# barometer.net
KiCad netlist of a schematic drawn in EAGLE
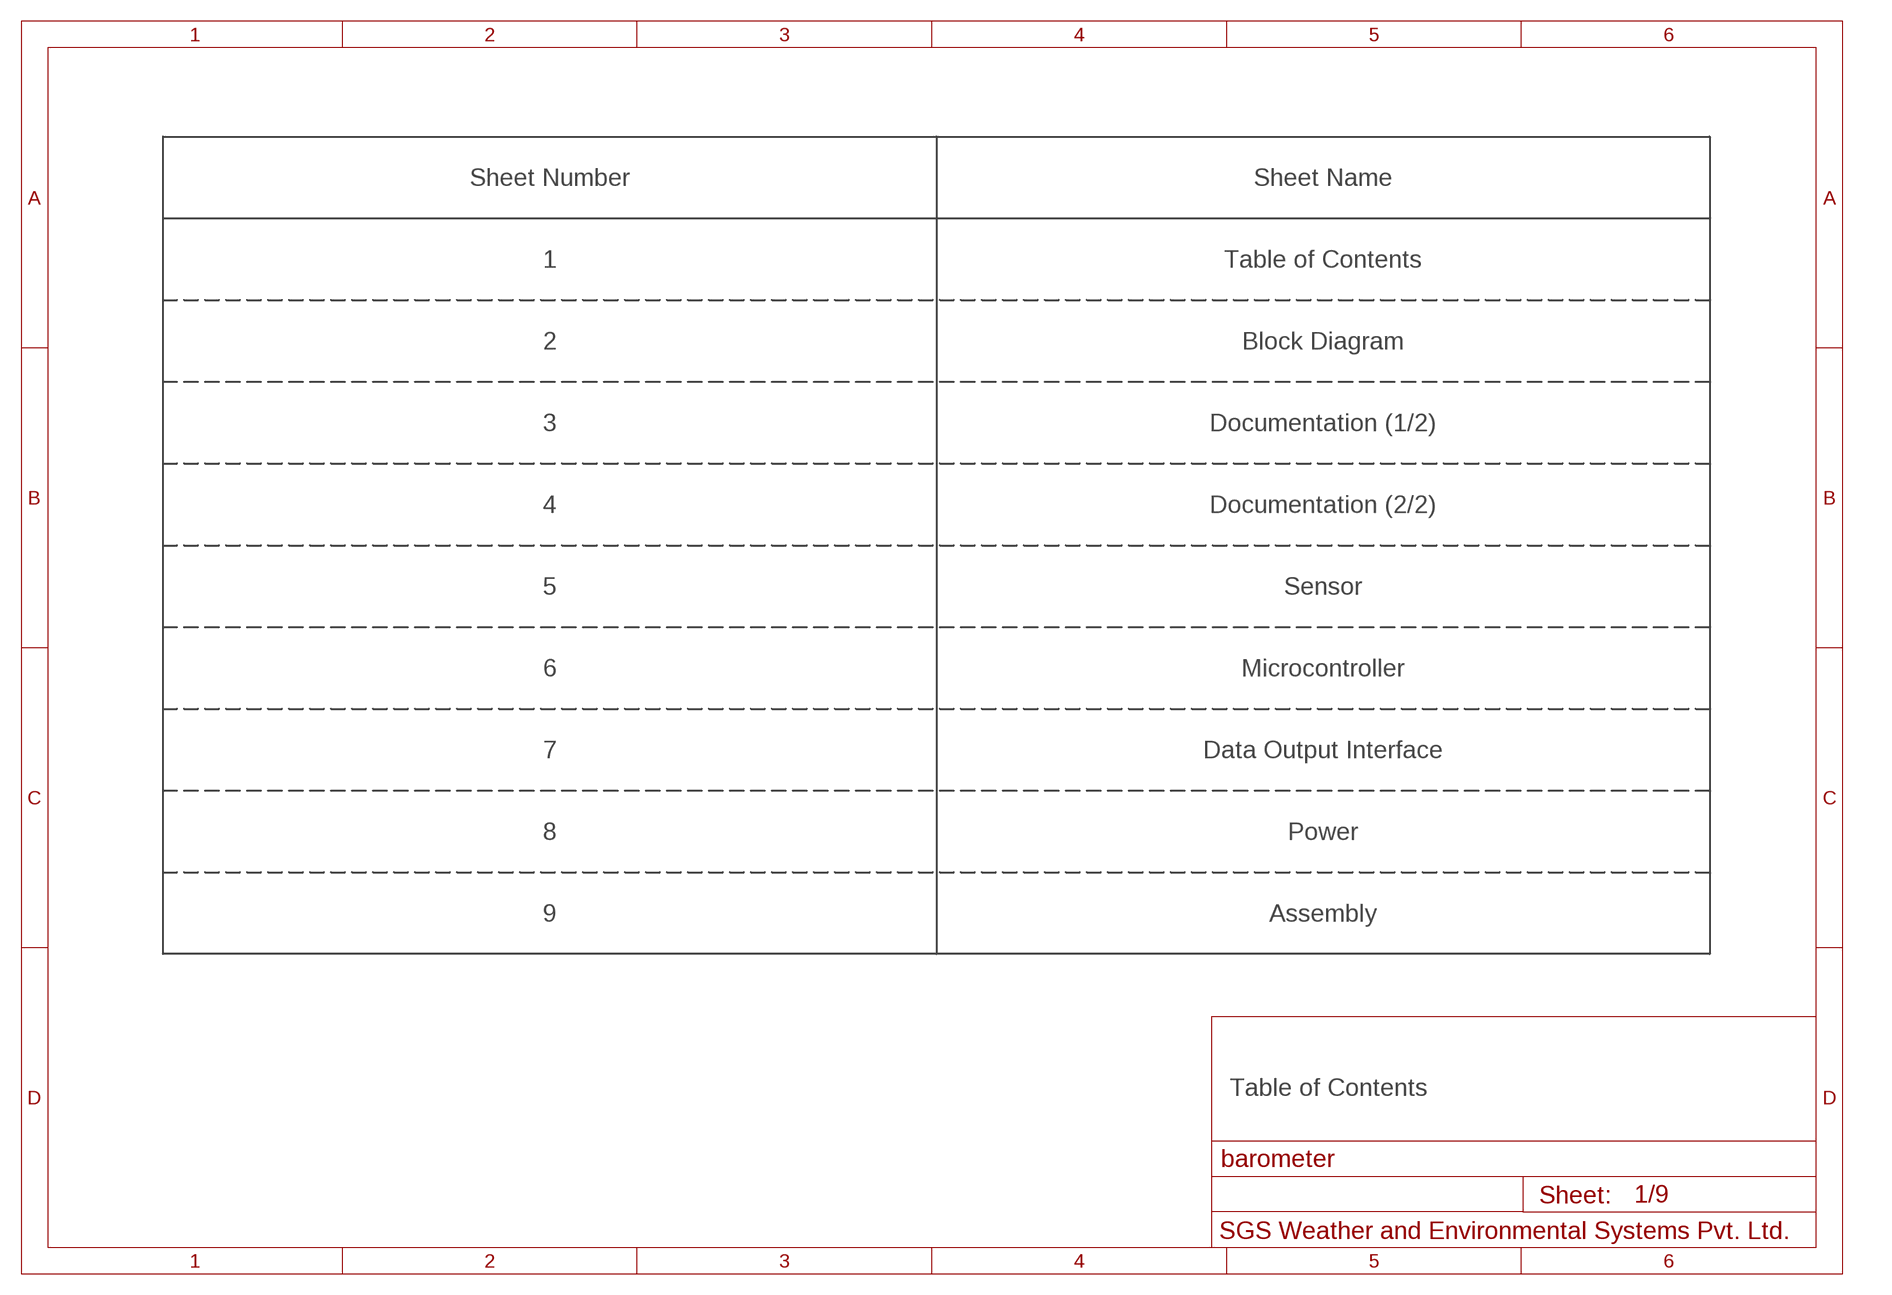
[diagram p0: schematic, sheet 1]
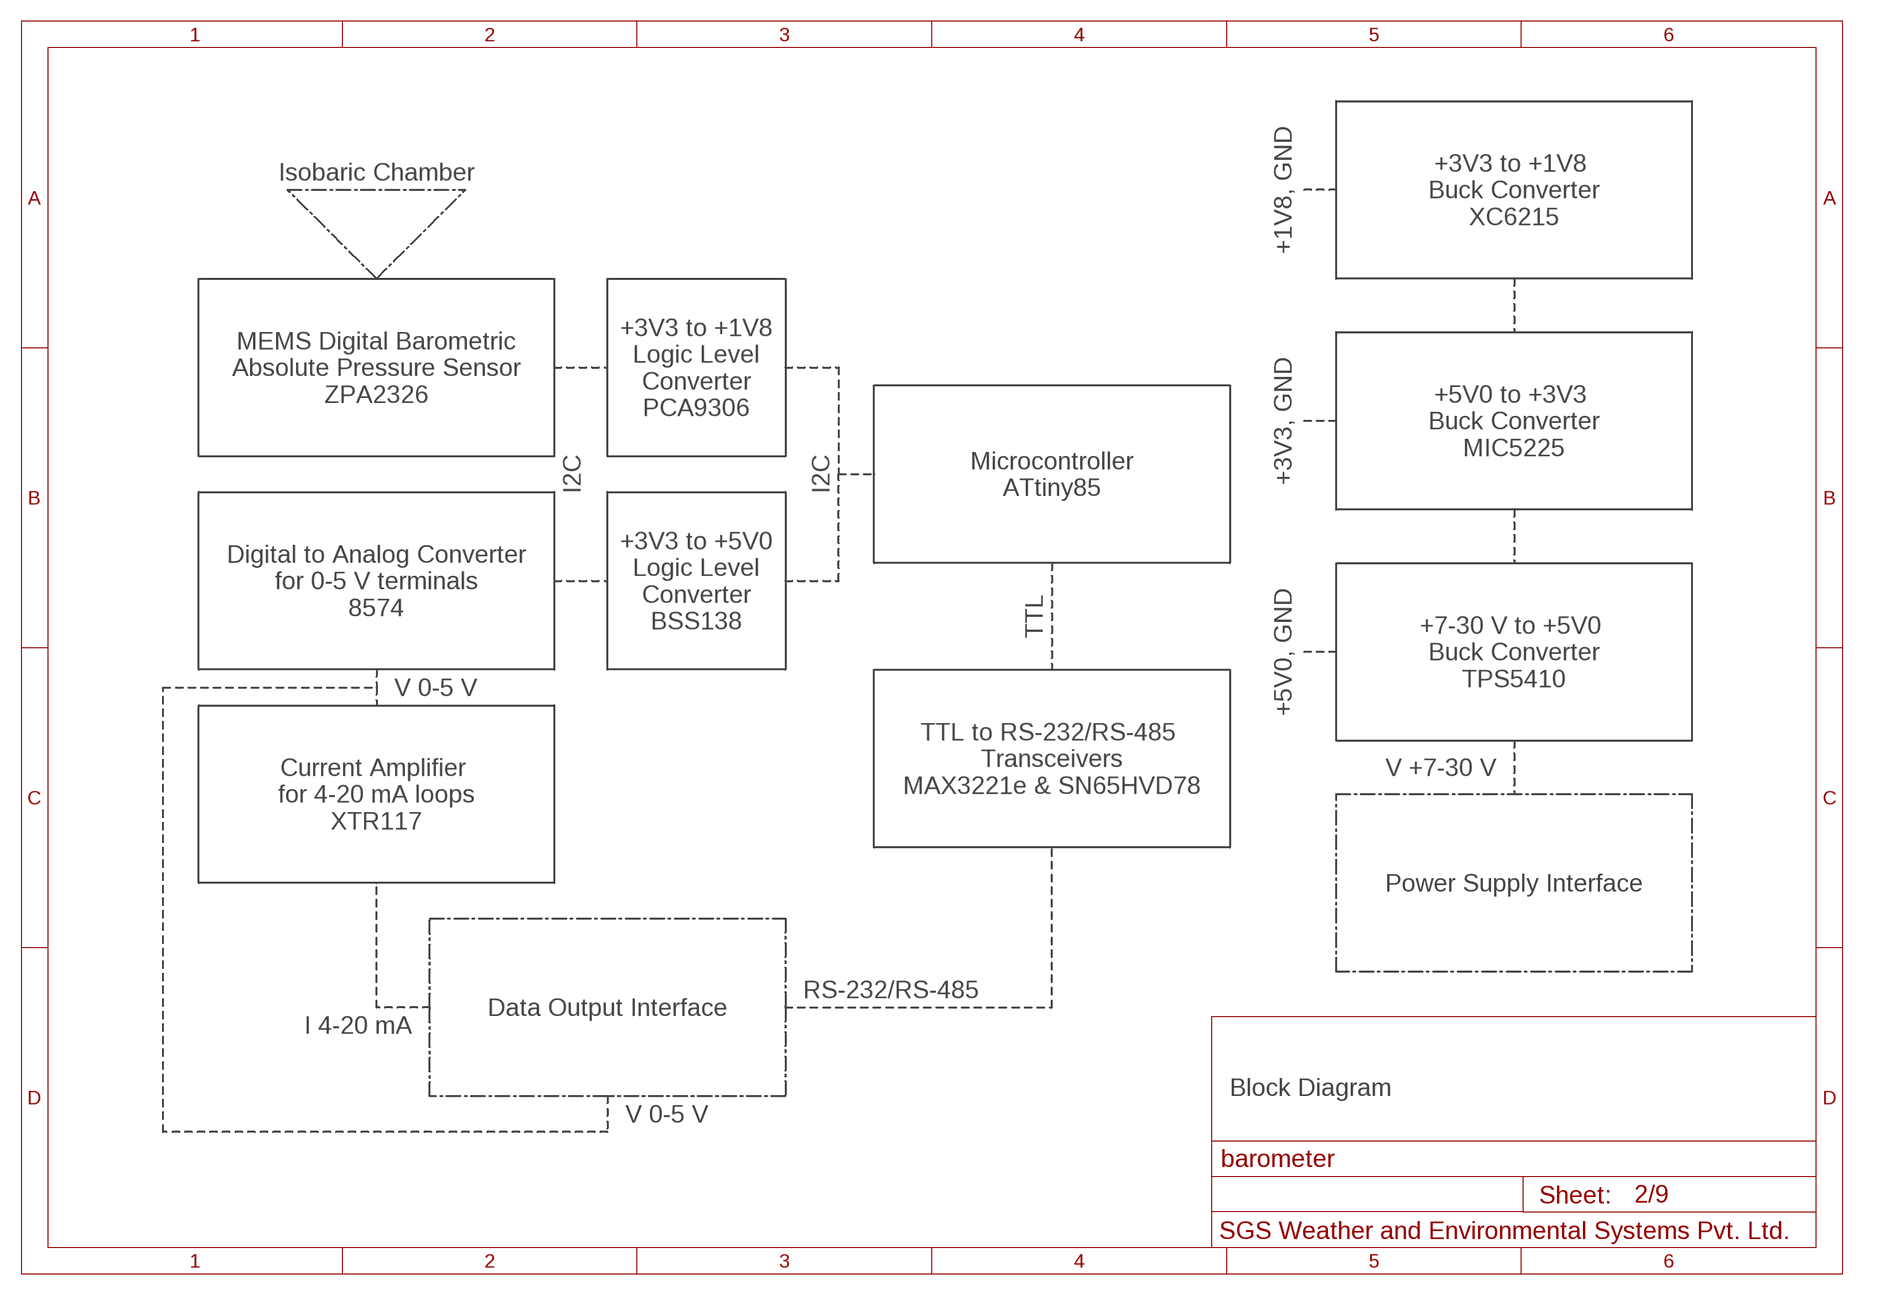
[diagram p1: schematic, sheet 2]
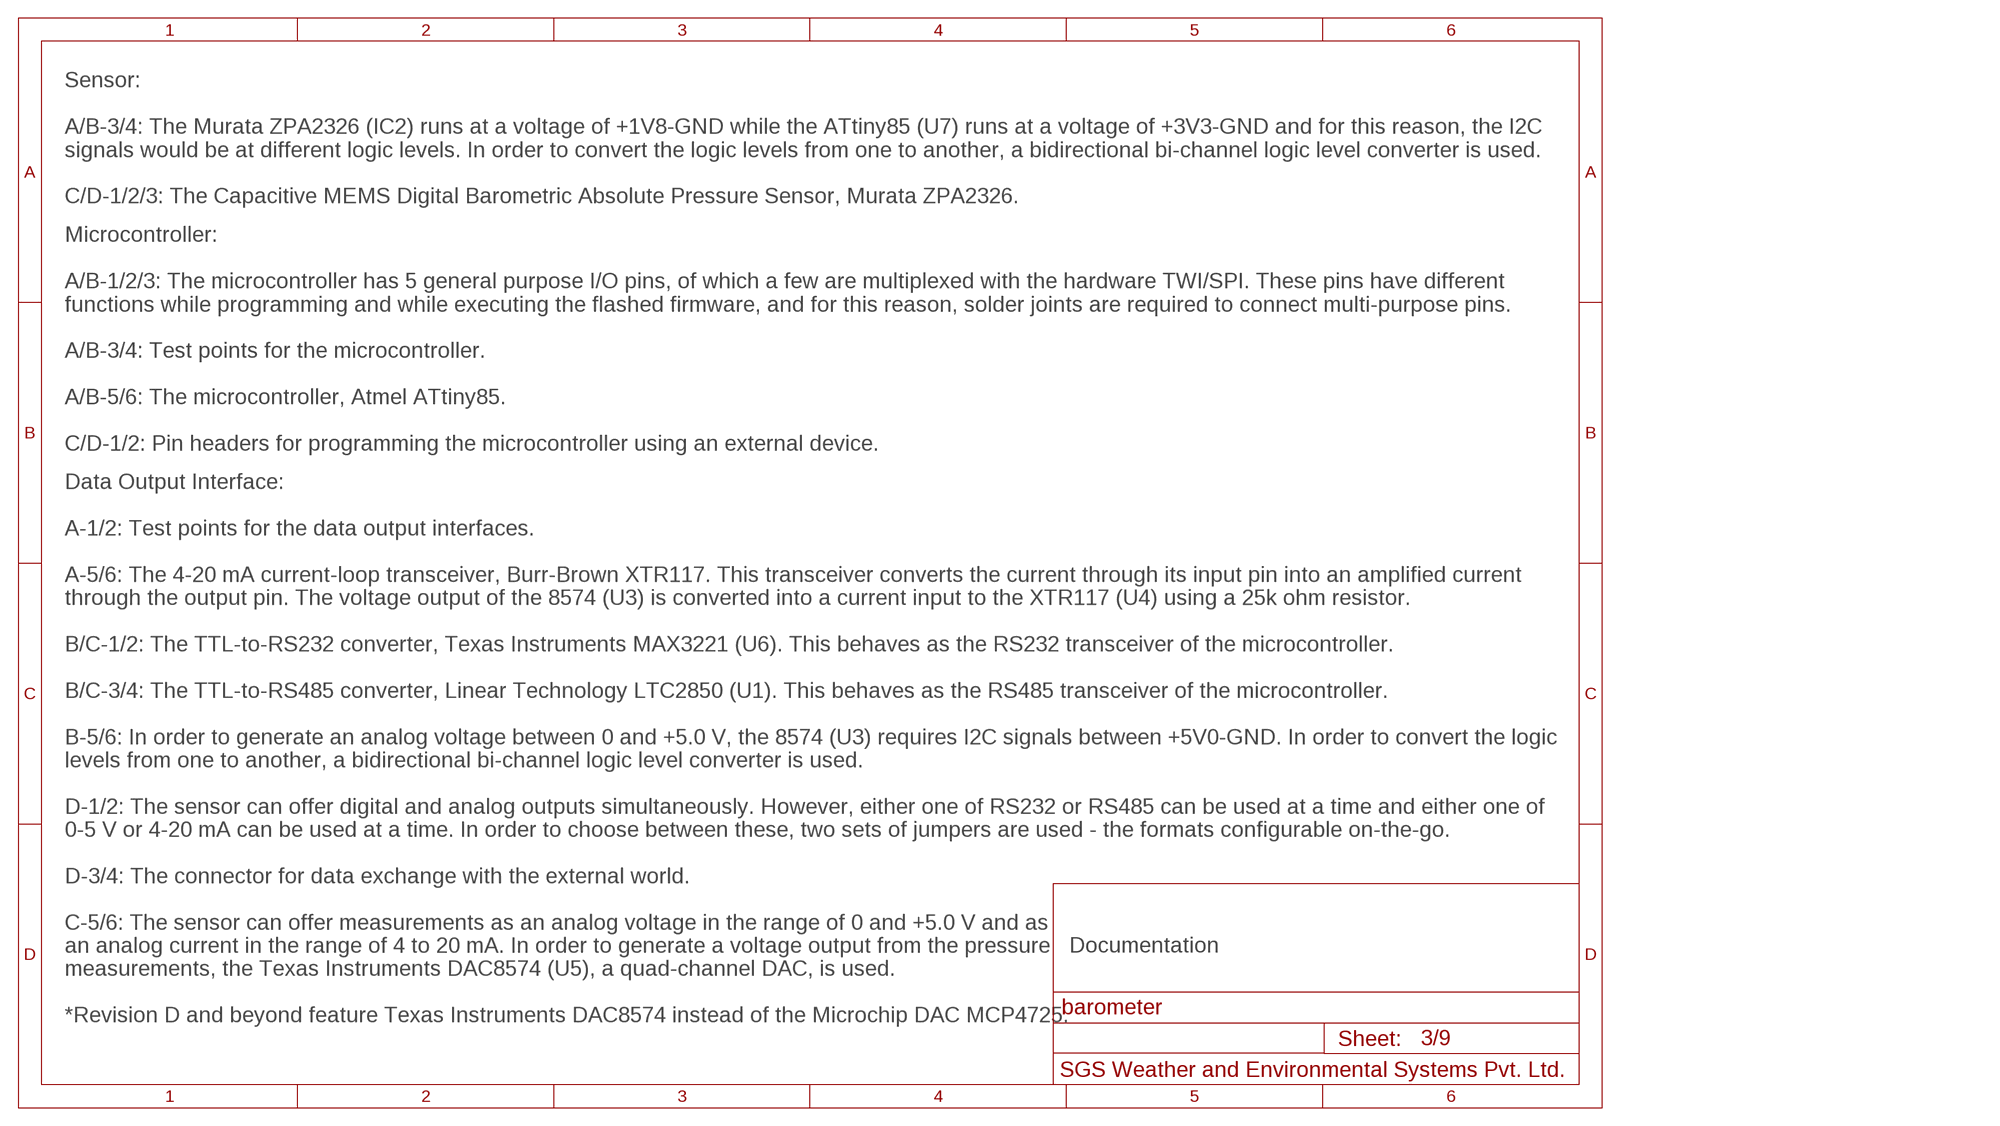
[diagram p2: schematic, sheet 3]
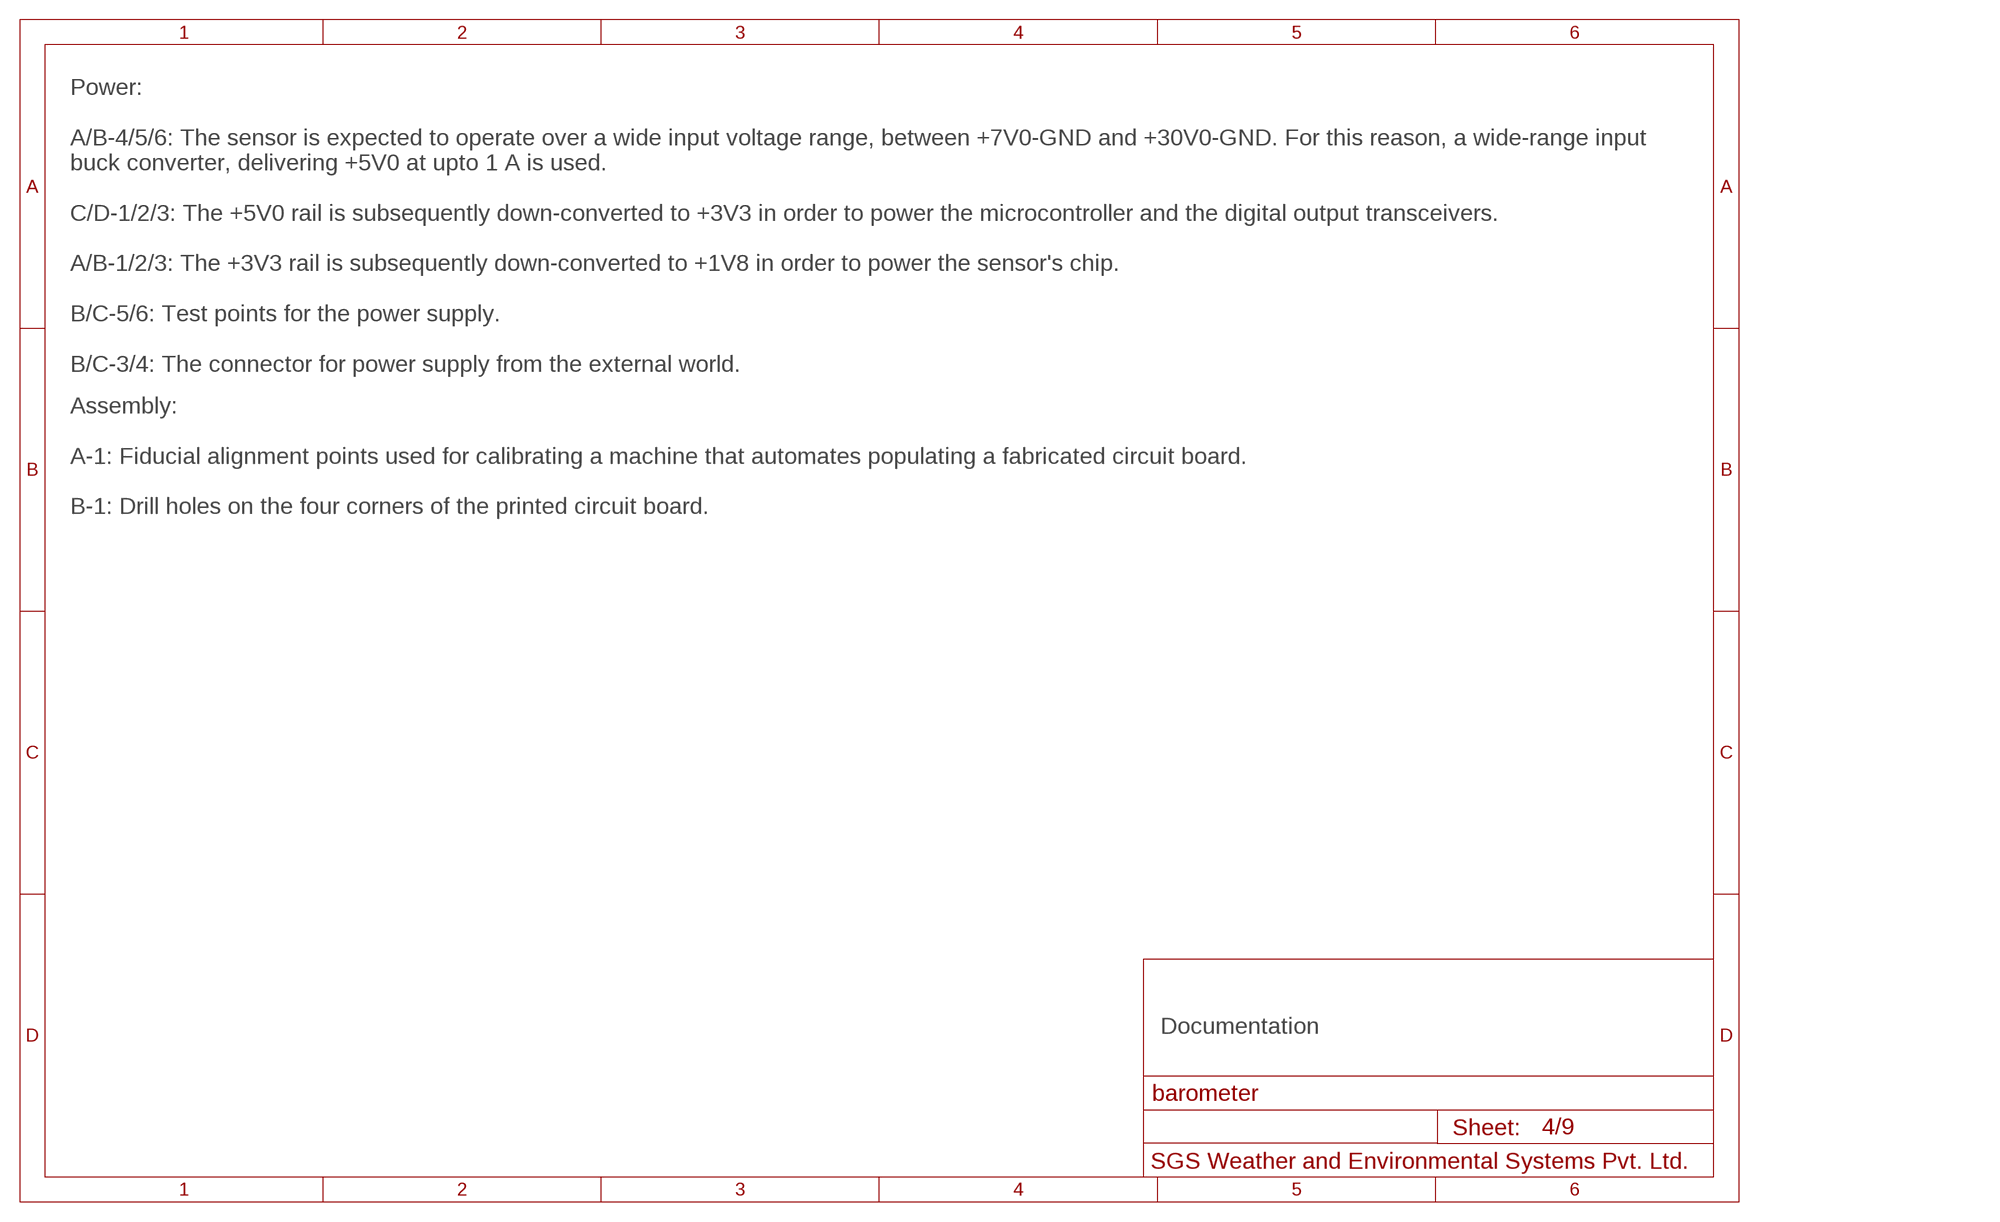
[diagram p3: schematic, sheet 4]
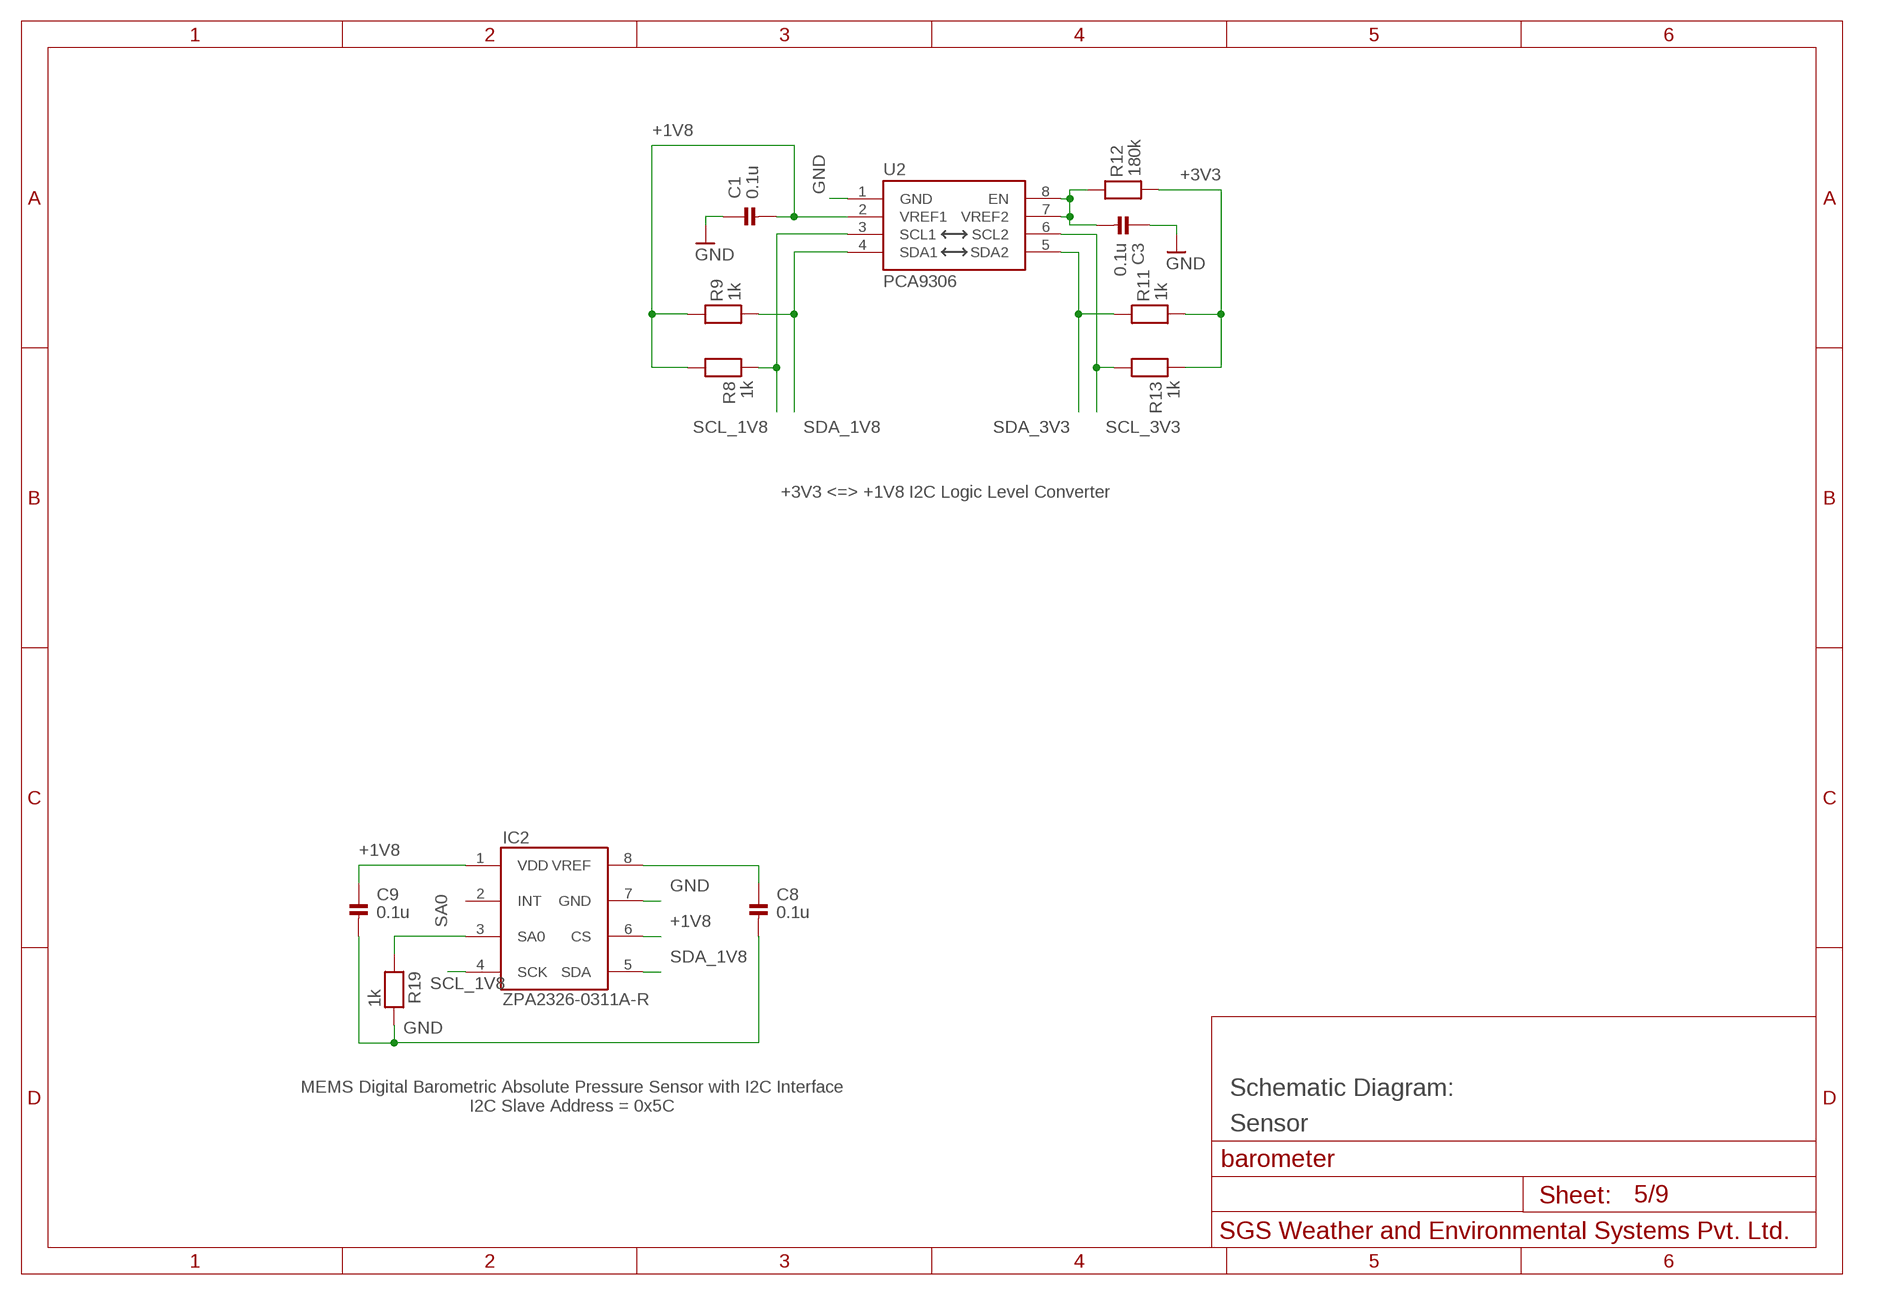
[diagram p4: schematic, sheet 5]
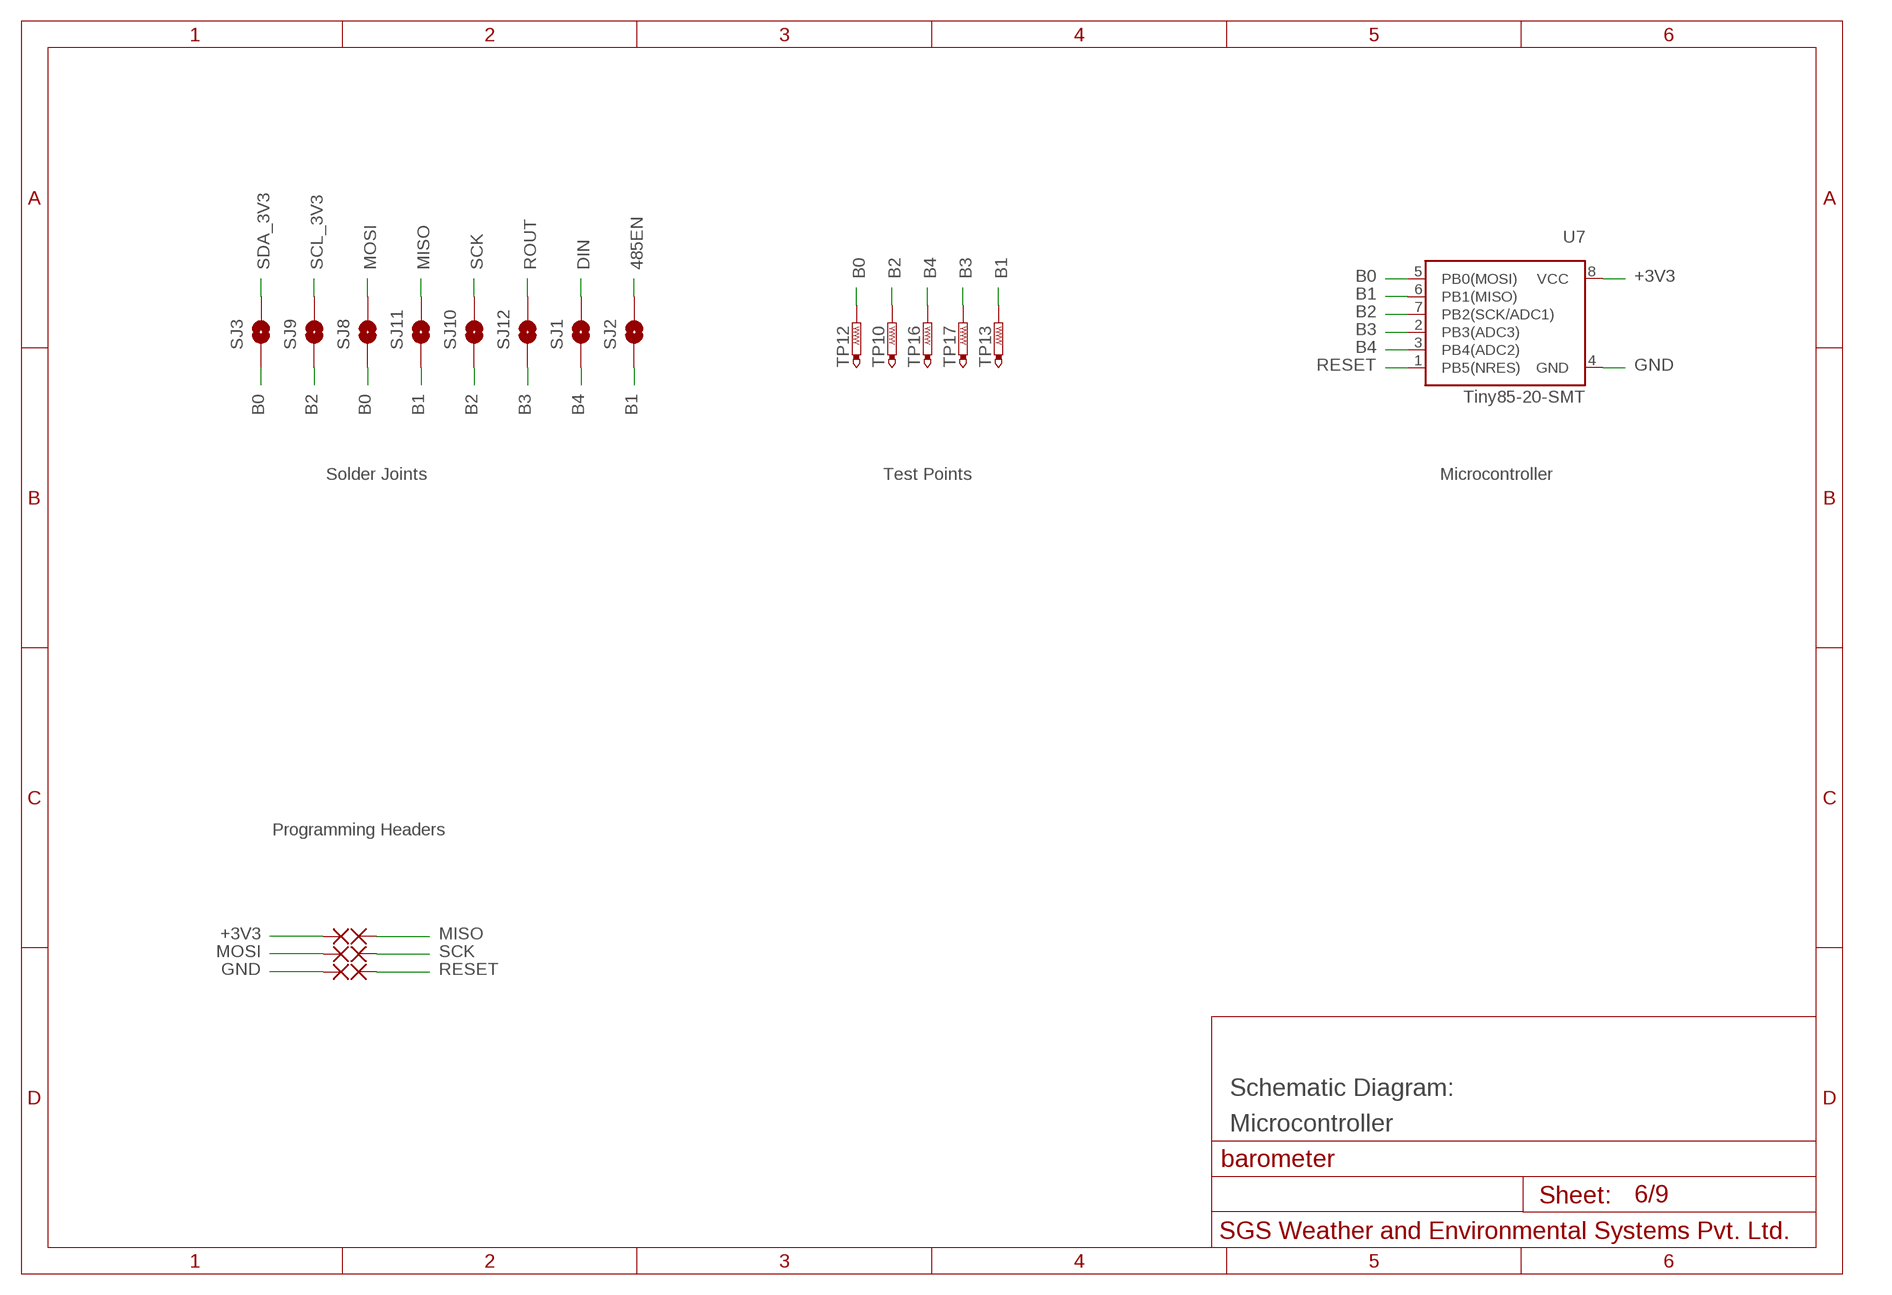
[diagram p5: schematic, sheet 6]
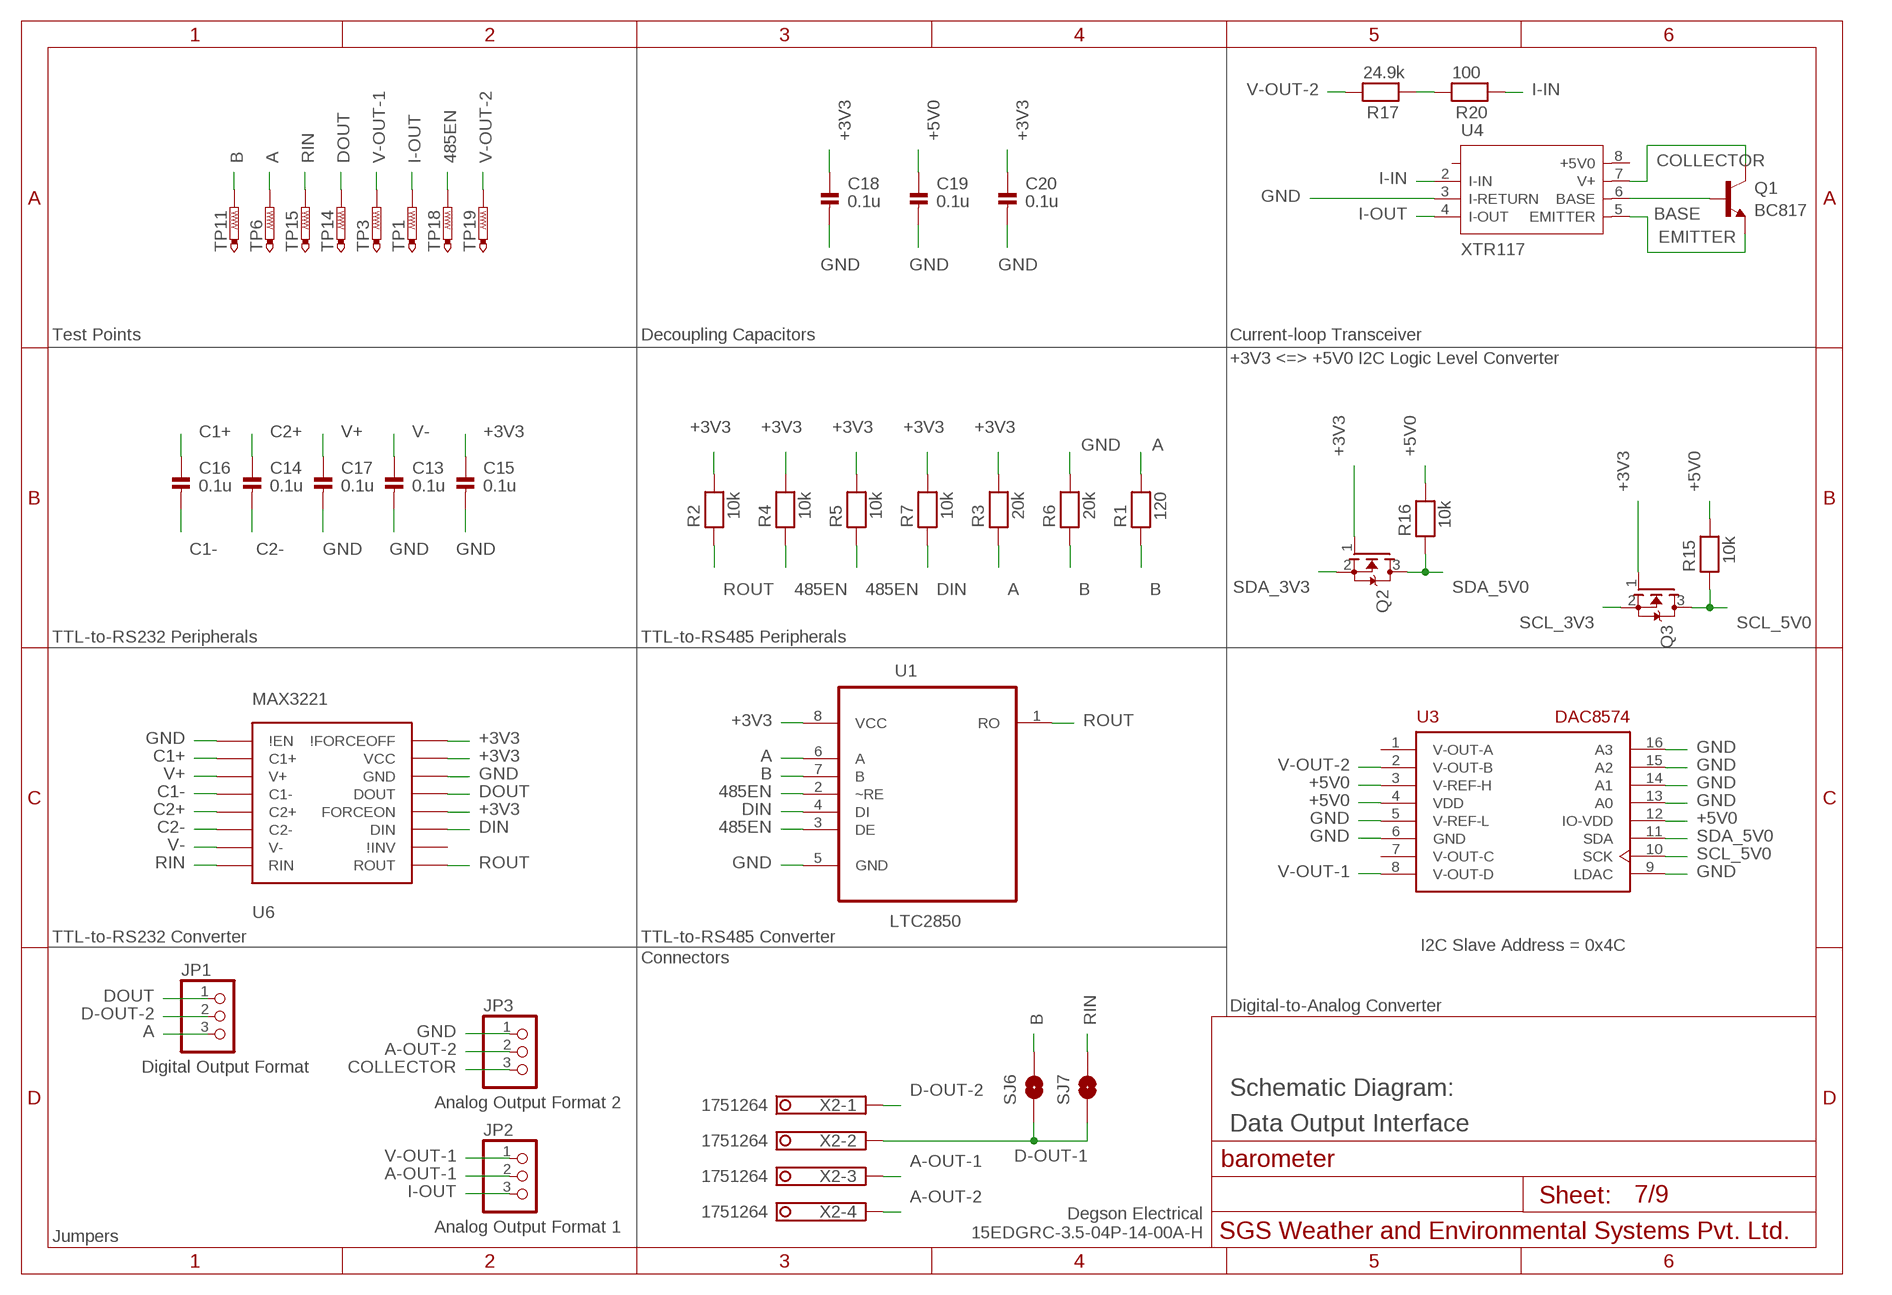
[diagram p6: schematic, sheet 7]
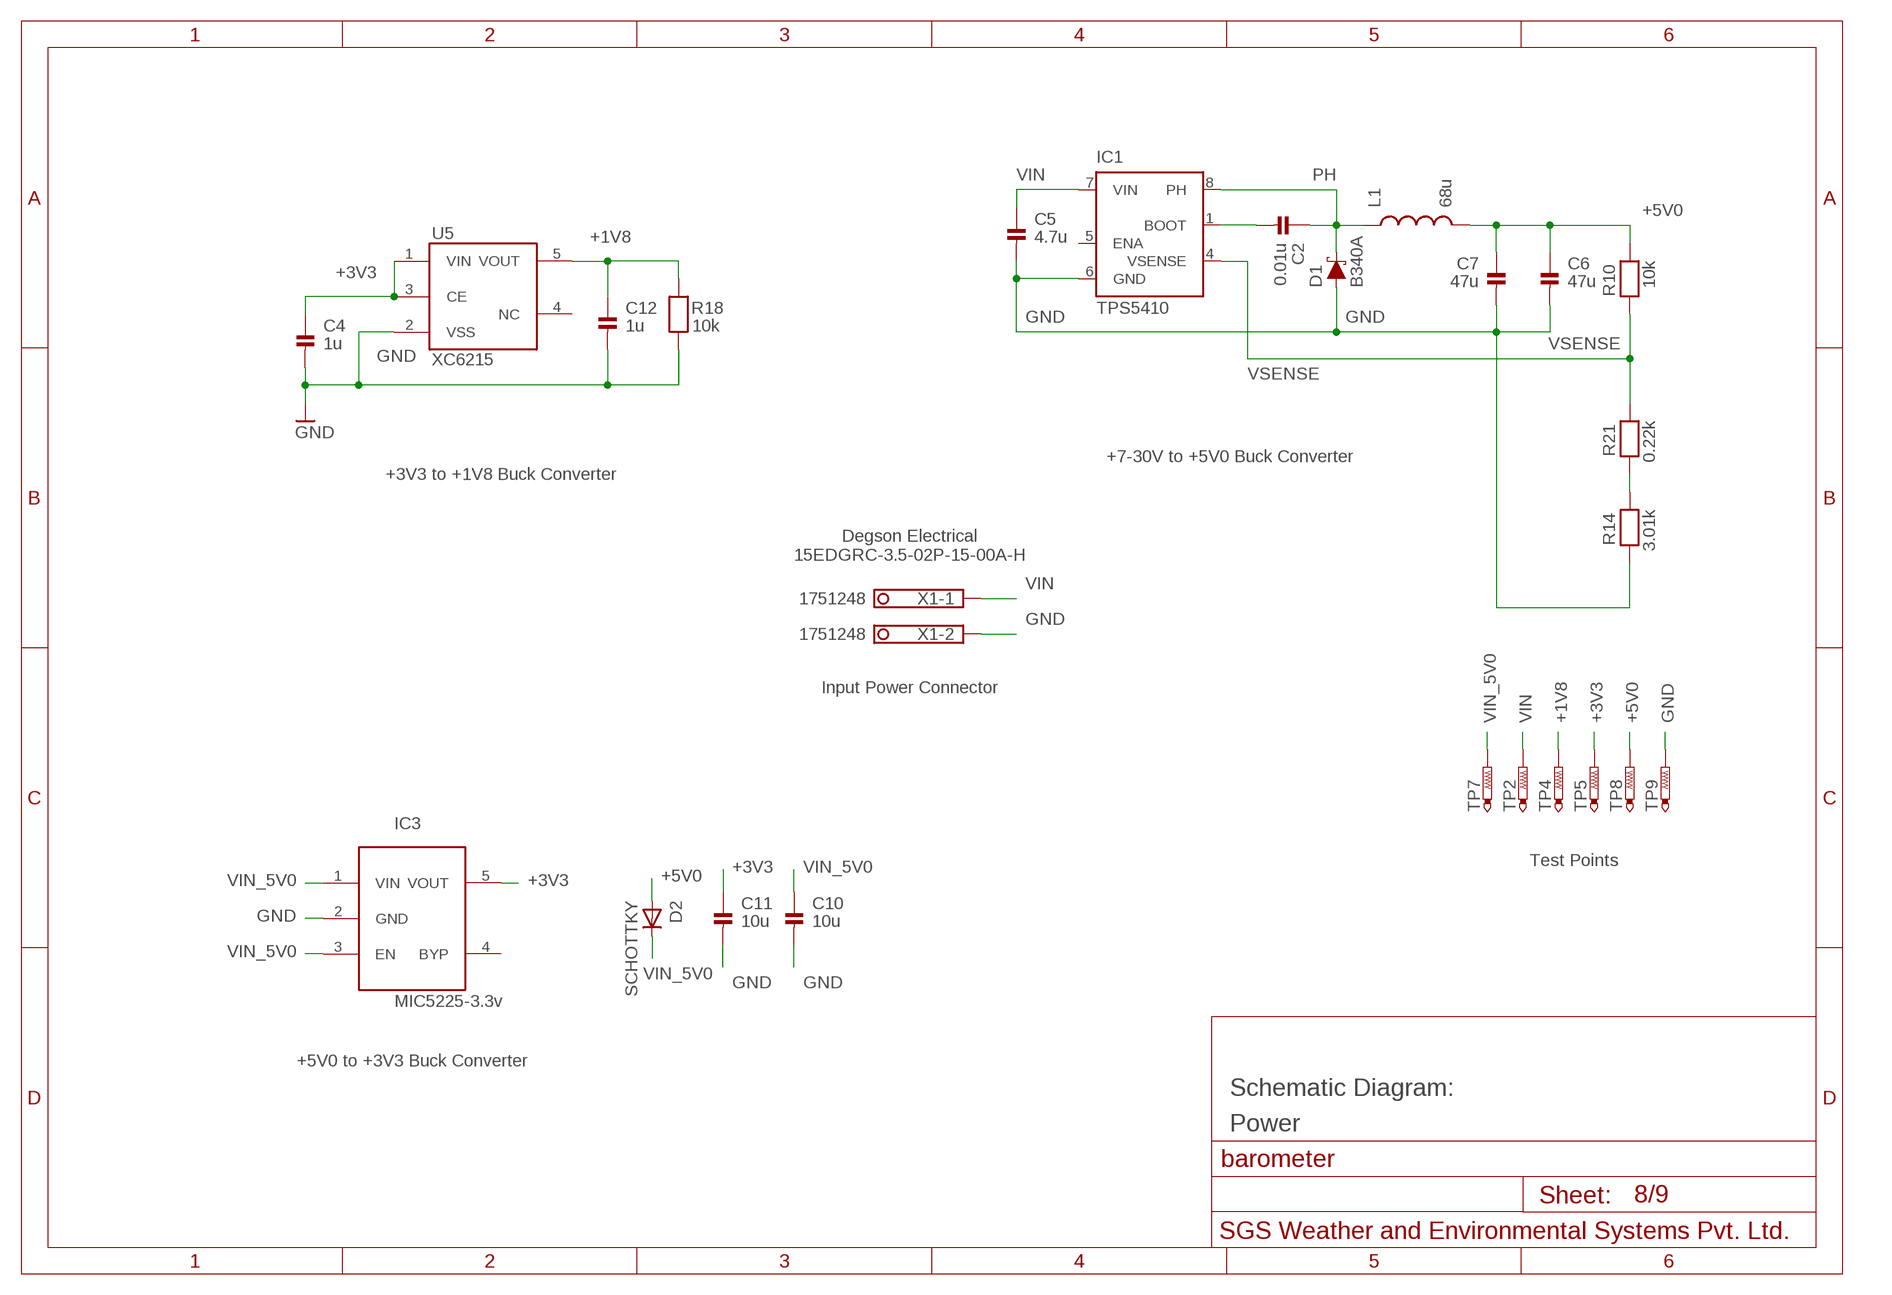
[diagram p7: schematic, sheet 8]
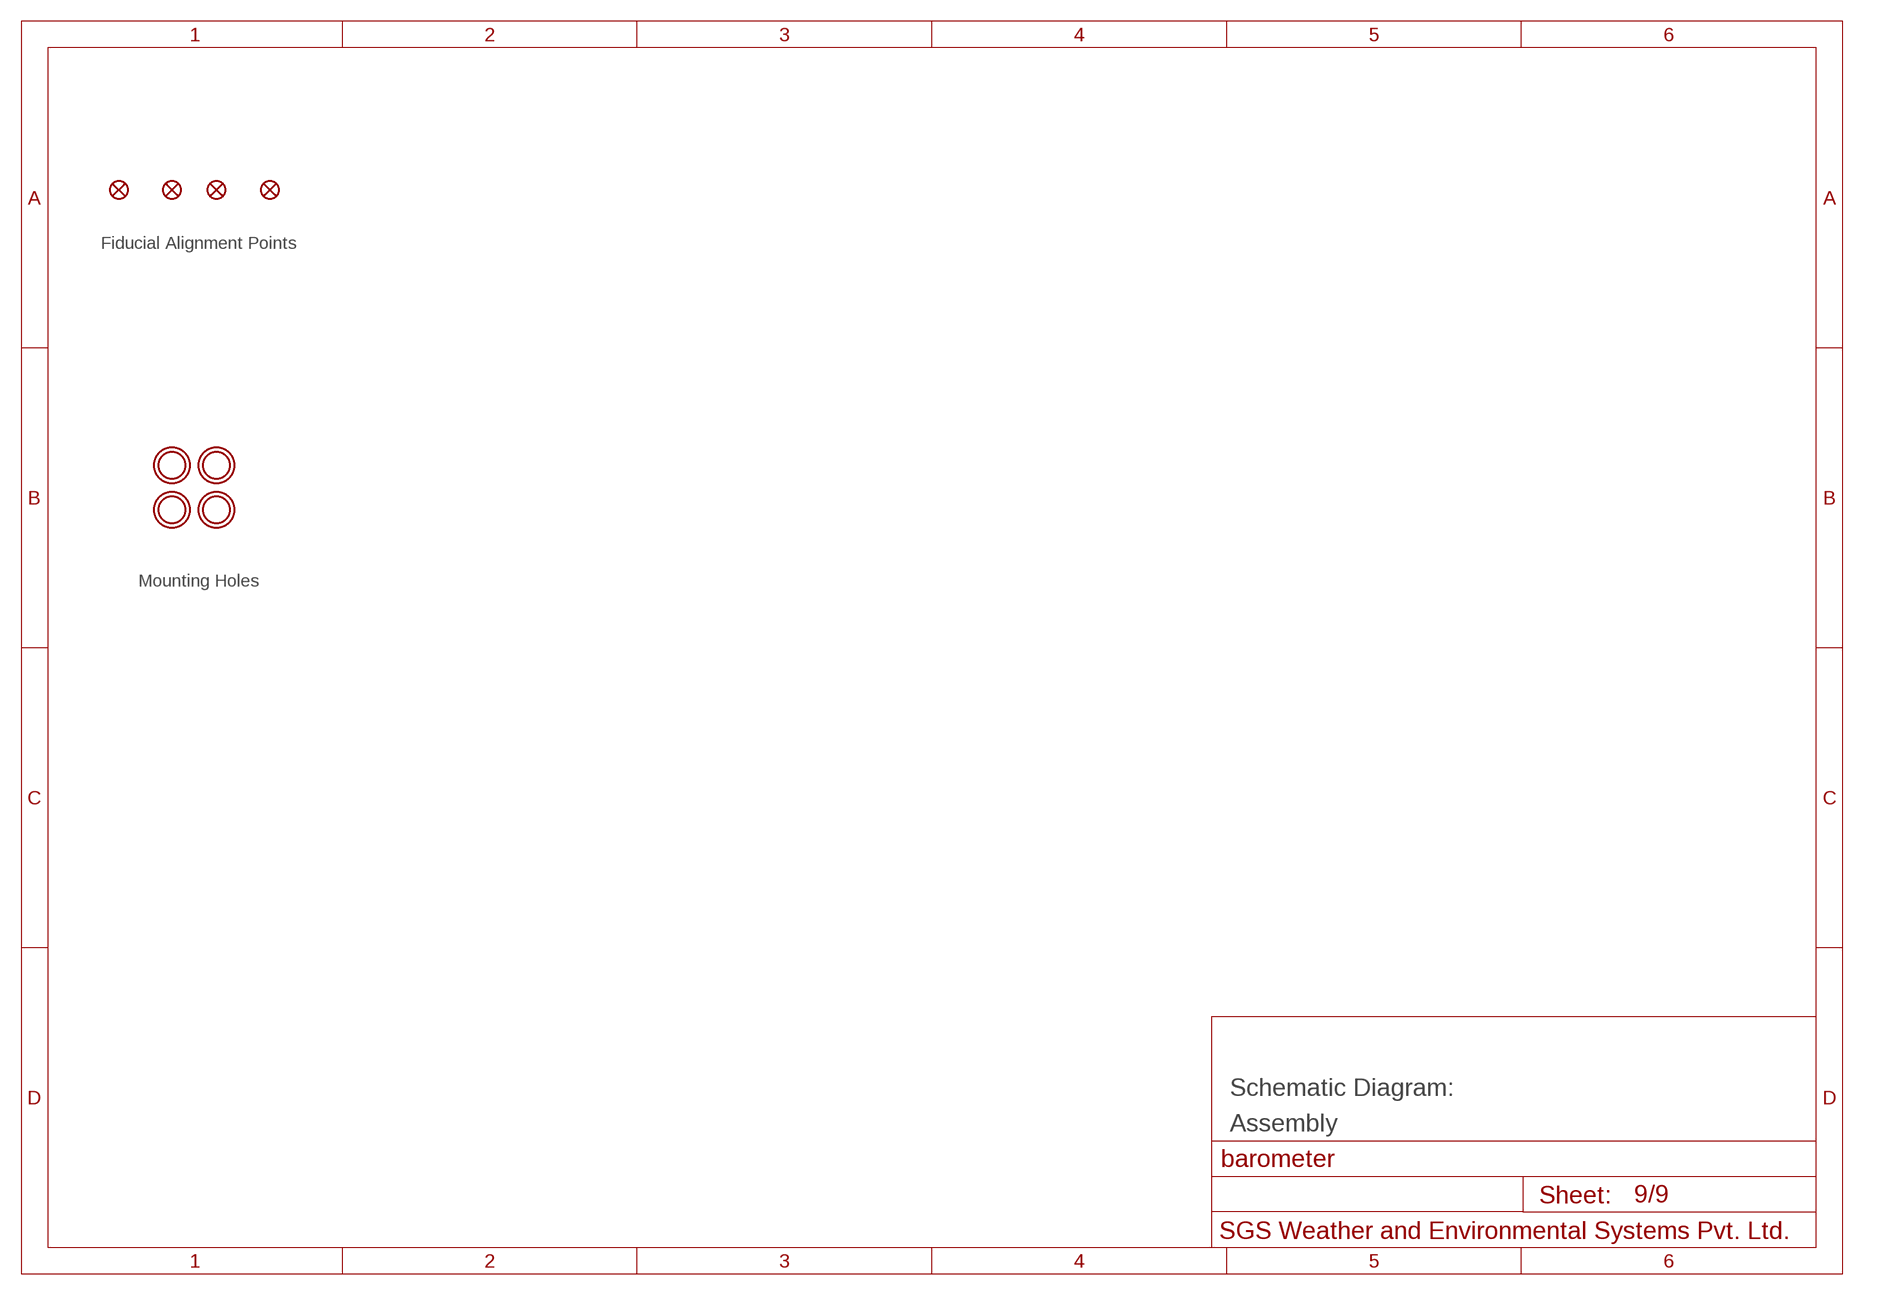
[diagram p8: schematic, sheet 9]

(export (version "E")
  (design (tool "Eeschema 10.0.6"))
  (components
    (comp (ref "C13")
      (value "0.1u")
      (footprint "eagle-import:0603")
      (libsource (lib "eagle-import") (part "CAP_CERAMIC0603"))
    )
    (comp (ref "C14")
      (value "0.1u")
      (footprint "eagle-import:0603")
      (libsource (lib "eagle-import") (part "CAP_CERAMIC0603"))
    )
    (comp (ref "C15")
      (value "0.1u")
      (footprint "eagle-import:0603")
      (libsource (lib "eagle-import") (part "CAP_CERAMIC0603"))
    )
    (comp (ref "C16")
      (value "0.1u")
      (footprint "eagle-import:0603")
      (libsource (lib "eagle-import") (part "CAP_CERAMIC0603"))
    )
    (comp (ref "C17")
      (value "0.1u")
      (footprint "eagle-import:0603")
      (libsource (lib "eagle-import") (part "CAP_CERAMIC0603"))
    )
    (comp (ref "C18")
      (value "0.1u")
      (footprint "eagle-import:0603")
      (libsource (lib "eagle-import") (part "CAP_CERAMIC0603"))
    )
    (comp (ref "C19")
      (value "0.1u")
      (footprint "eagle-import:0603")
      (libsource (lib "eagle-import") (part "CAP_CERAMIC0603"))
    )
    (comp (ref "C20")
      (value "0.1u")
      (footprint "eagle-import:0603")
      (libsource (lib "eagle-import") (part "CAP_CERAMIC0603"))
    )
    (comp (ref "JP1")
      (value "Digital Output Format")
      (footprint "eagle-import:1X03_SMT")
      (libsource (lib "eagle-import") (part "HEADER-1X3SMT"))
    )
    (comp (ref "JP2")
      (value "Analog Output Format 1")
      (footprint "eagle-import:1X03_SMT")
      (libsource (lib "eagle-import") (part "HEADER-1X3SMT"))
    )
    (comp (ref "JP3")
      (value "Analog Output Format 2")
      (footprint "eagle-import:1X03_SMT")
      (libsource (lib "eagle-import") (part "HEADER-1X3SMT"))
    )
    (comp (ref "Q1")
      (value "BC817")
      (footprint "eagle-import:SOT23-WIDE")
      (libsource (lib "eagle-import") (part "TRANSISTOR_NPNWIDE"))
    )
    (comp (ref "Q2")
      (value "MOSFET-NWIDE")
      (footprint "eagle-import:SOT23-WIDE")
      (libsource (lib "eagle-import") (part "MOSFET-NWIDE"))
    )
    (comp (ref "Q3")
      (value "MOSFET-NWIDE")
      (footprint "eagle-import:SOT23-WIDE")
      (libsource (lib "eagle-import") (part "MOSFET-NWIDE"))
    )
    (comp (ref "R1")
      (value "120")
      (footprint "eagle-import:0603")
      (libsource (lib "eagle-import") (part "RESISTOR0603"))
    )
    (comp (ref "R2")
      (value "10k")
      (footprint "eagle-import:0603")
      (libsource (lib "eagle-import") (part "RESISTOR0603"))
    )
    (comp (ref "R3")
      (value "20k")
      (footprint "eagle-import:0603")
      (libsource (lib "eagle-import") (part "RESISTOR0603"))
    )
    (comp (ref "R4")
      (value "10k")
      (footprint "eagle-import:0603")
      (libsource (lib "eagle-import") (part "RESISTOR0603"))
    )
    (comp (ref "R5")
      (value "10k")
      (footprint "eagle-import:0603")
      (libsource (lib "eagle-import") (part "RESISTOR0603"))
    )
    (comp (ref "R6")
      (value "20k")
      (footprint "eagle-import:0603")
      (libsource (lib "eagle-import") (part "RESISTOR0603"))
    )
    (comp (ref "R7")
      (value "10k")
      (footprint "eagle-import:0603")
      (libsource (lib "eagle-import") (part "RESISTOR0603"))
    )
    (comp (ref "R15")
      (value "10k")
      (footprint "eagle-import:0603")
      (libsource (lib "eagle-import") (part "RESISTOR0603"))
    )
    (comp (ref "R16")
      (value "10k")
      (footprint "eagle-import:0603")
      (libsource (lib "eagle-import") (part "RESISTOR0603"))
    )
    (comp (ref "R17")
      (value "24.9k")
      (footprint "eagle-import:0603")
      (libsource (lib "eagle-import") (part "RESISTOR0603"))
    )
    (comp (ref "R20")
      (value "100")
      (footprint "eagle-import:0603")
      (libsource (lib "eagle-import") (part "RESISTOR0603"))
    )
    (comp (ref "SJ6")
      (value "SOLDERJUMPERTRACE")
      (footprint "eagle-import:SJ_2S-TRACE")
      (libsource (lib "eagle-import") (part "SOLDERJUMPERTRACE"))
    )
    (comp (ref "SJ7")
      (value "SOLDERJUMPERTRACE")
      (footprint "eagle-import:SJ_2S-TRACE")
      (libsource (lib "eagle-import") (part "SOLDERJUMPERTRACE"))
    )
    (comp (ref "TP1")
      (value "PTR1B1,27")
      (footprint "eagle-import:B1,27")
      (libsource (lib "eagle-import") (part "PTR1B1,27"))
    )
    (comp (ref "TP3")
      (value "PTR1B1,27")
      (footprint "eagle-import:B1,27")
      (libsource (lib "eagle-import") (part "PTR1B1,27"))
    )
    (comp (ref "TP6")
      (value "PTR1B1,27")
      (footprint "eagle-import:B1,27")
      (libsource (lib "eagle-import") (part "PTR1B1,27"))
    )
    (comp (ref "TP11")
      (value "PTR1B1,27")
      (footprint "eagle-import:B1,27")
      (libsource (lib "eagle-import") (part "PTR1B1,27"))
    )
    (comp (ref "TP14")
      (value "PTR1B1,27")
      (footprint "eagle-import:B1,27")
      (libsource (lib "eagle-import") (part "PTR1B1,27"))
    )
    (comp (ref "TP15")
      (value "PTR1B1,27")
      (footprint "eagle-import:B1,27")
      (libsource (lib "eagle-import") (part "PTR1B1,27"))
    )
    (comp (ref "TP18")
      (value "PTR1B1,27")
      (footprint "eagle-import:B1,27")
      (libsource (lib "eagle-import") (part "PTR1B1,27"))
    )
    (comp (ref "TP19")
      (value "PTR1B1,27")
      (footprint "eagle-import:B1,27")
      (libsource (lib "eagle-import") (part "PTR1B1,27"))
    )
    (comp (ref "U1")
      (value "LTC2850")
      (footprint "eagle-import:SOIC127P600X175-8N")
      (fields (field (name "MPN") "LTC2850IS8#PBF"))
      (libsource (lib "eagle-import") (part "LTC2850IS8PBF"))
    )
    (comp (ref "U3")
      (value "DAC8574")
      (footprint "eagle-import:TSSOP16")
      (libsource (lib "eagle-import") (part "DAC8574"))
    )
    (comp (ref "U4")
      (value "XTR117")
      (footprint "eagle-import:MSOP8-0.65-3X3MM")
      (libsource (lib "eagle-import") (part "TRANSCEIVER-XTR117"))
    )
    (comp (ref "U6")
      (value "MAX3221")
      (footprint "eagle-import:TSSOP16")
      (libsource (lib "eagle-import") (part "MAX3221-TSSOP16"))
    )
    (comp (ref "X2")
      (value "1751264")
      (footprint "eagle-import:1751264")
      (libsource (lib "eagle-import") (part "1751264"))
    )
    (comp (ref "C1")
      (value "0.1u")
      (footprint "eagle-import:0603")
      (libsource (lib "eagle-import") (part "CAP_CERAMIC0603"))
    )
    (comp (ref "C3")
      (value "0.1u")
      (footprint "eagle-import:0603")
      (libsource (lib "eagle-import") (part "CAP_CERAMIC0603"))
    )
    (comp (ref "C8")
      (value "0.1u")
      (footprint "eagle-import:0603")
      (libsource (lib "eagle-import") (part "CAP_CERAMIC0603"))
    )
    (comp (ref "C9")
      (value "0.1u")
      (footprint "eagle-import:0603")
      (libsource (lib "eagle-import") (part "CAP_CERAMIC0603"))
    )
    (comp (ref "IC2")
      (value "ZPA2326-0311A-R")
      (footprint "eagle-import:2326")
      (libsource (lib "eagle-import") (part "ZPA2326-0311A-R"))
    )
    (comp (ref "R8")
      (value "1k")
      (footprint "eagle-import:0603")
      (libsource (lib "eagle-import") (part "RESISTOR0603"))
    )
    (comp (ref "R9")
      (value "1k")
      (footprint "eagle-import:0603")
      (libsource (lib "eagle-import") (part "RESISTOR0603"))
    )
    (comp (ref "R11")
      (value "1k")
      (footprint "eagle-import:0603")
      (libsource (lib "eagle-import") (part "RESISTOR0603"))
    )
    (comp (ref "R12")
      (value "180k")
      (footprint "eagle-import:0603")
      (libsource (lib "eagle-import") (part "RESISTOR0603"))
    )
    (comp (ref "R13")
      (value "1k")
      (footprint "eagle-import:0603")
      (libsource (lib "eagle-import") (part "RESISTOR0603"))
    )
    (comp (ref "R19")
      (value "1k")
      (footprint "eagle-import:0603")
      (libsource (lib "eagle-import") (part "RESISTOR0603"))
    )
    (comp (ref "U2")
      (value "PCA9306")
      (footprint "eagle-import:PSOP-8")
      (libsource (lib "eagle-import") (part "PCA9306"))
    )
    (comp (ref "C2")
      (value "0.01u")
      (footprint "eagle-import:0603")
      (libsource (lib "eagle-import") (part "CAP_CERAMIC0603"))
    )
    (comp (ref "C4")
      (value "1u")
      (footprint "eagle-import:0603")
      (libsource (lib "eagle-import") (part "CAP_CERAMIC0603"))
    )
    (comp (ref "C5")
      (value "4.7u")
      (footprint "eagle-import:0805")
      (libsource (lib "eagle-import") (part "CAP_CERAMIC0805"))
    )
    (comp (ref "C6")
      (value "47u")
      (footprint "eagle-import:1206")
      (libsource (lib "eagle-import") (part "CAP_CERAMIC1206"))
    )
    (comp (ref "C7")
      (value "47u")
      (footprint "eagle-import:1206")
      (libsource (lib "eagle-import") (part "CAP_CERAMIC1206"))
    )
    (comp (ref "C10")
      (value "10u")
      (footprint "eagle-import:0603")
      (libsource (lib "eagle-import") (part "CAP_CERAMIC0603"))
    )
    (comp (ref "C11")
      (value "10u")
      (footprint "eagle-import:0603")
      (libsource (lib "eagle-import") (part "CAP_CERAMIC0603"))
    )
    (comp (ref "C12")
      (value "1u")
      (footprint "eagle-import:0603")
      (libsource (lib "eagle-import") (part "CAP_CERAMIC0603"))
    )
    (comp (ref "D1")
      (value "B340A")
      (footprint "eagle-import:SMA-DIODE")
      (libsource (lib "eagle-import") (part "DIODE-SCHOTTKY-B340A"))
    )
    (comp (ref "D2")
      (value "SCHOTTKY")
      (footprint "eagle-import:SOD-123FL")
      (libsource (lib "eagle-import") (part "DIODE_SOD-123FL"))
    )
    (comp (ref "IC1")
      (value "TPS5410")
      (footprint "eagle-import:D_R-PDSO-G08")
      (fields (field (name "MPN") "TPS5410DR"))
      (libsource (lib "eagle-import") (part "TPS5410"))
    )
    (comp (ref "IC3")
      (value "MIC5225-3.3v")
      (footprint "eagle-import:SOT23-5L")
      (libsource (lib "eagle-import") (part "LP298XS"))
    )
    (comp (ref "L1")
      (value "68u")
      (footprint "eagle-import:VLS6045EX")
      (libsource (lib "eagle-import") (part "INDUCTOR-TDKVLS6045EX"))
    )
    (comp (ref "R10")
      (value "10k")
      (footprint "eagle-import:0603")
      (libsource (lib "eagle-import") (part "RESISTOR0603"))
    )
    (comp (ref "R14")
      (value "3.01k")
      (footprint "eagle-import:0603")
      (libsource (lib "eagle-import") (part "RESISTOR0603"))
    )
    (comp (ref "R18")
      (value "10k")
      (footprint "eagle-import:0603")
      (libsource (lib "eagle-import") (part "RESISTOR0603"))
    )
    (comp (ref "R21")
      (value "0.22k")
      (footprint "eagle-import:0603")
      (libsource (lib "eagle-import") (part "RESISTOR0603"))
    )
    (comp (ref "TP2")
      (value "PTR1B1,27")
      (footprint "eagle-import:B1,27")
      (libsource (lib "eagle-import") (part "PTR1B1,27"))
    )
    (comp (ref "TP4")
      (value "PTR1B1,27")
      (footprint "eagle-import:B1,27")
      (libsource (lib "eagle-import") (part "PTR1B1,27"))
    )
    (comp (ref "TP5")
      (value "PTR1B1,27")
      (footprint "eagle-import:B1,27")
      (libsource (lib "eagle-import") (part "PTR1B1,27"))
    )
    (comp (ref "TP7")
      (value "PTR1B1,27")
      (footprint "eagle-import:B1,27")
      (libsource (lib "eagle-import") (part "PTR1B1,27"))
    )
    (comp (ref "TP8")
      (value "PTR1B1,27")
      (footprint "eagle-import:B1,27")
      (libsource (lib "eagle-import") (part "PTR1B1,27"))
    )
    (comp (ref "TP9")
      (value "PTR1B1,27")
      (footprint "eagle-import:B1,27")
      (libsource (lib "eagle-import") (part "PTR1B1,27"))
    )
    (comp (ref "U5")
      (value "XC6215XC6215B182NR")
      (footprint "eagle-import:SOT25")
      (libsource (lib "eagle-import") (part "XC6215XC6215B182NR"))
    )
    (comp (ref "X1")
      (value "1751248")
      (footprint "eagle-import:1751248")
      (libsource (lib "eagle-import") (part "1751248"))
    )
    (comp (ref "FID1")
      (value "FIDUCIAL1X2.5")
      (footprint "eagle-import:FIDUCIAL-1X2.5")
      (libsource (lib "eagle-import") (part "FIDUCIAL1X2.5"))
    )
    (comp (ref "FID2")
      (value "FIDUCIAL1X2.5")
      (footprint "eagle-import:FIDUCIAL-1X2.5")
      (libsource (lib "eagle-import") (part "FIDUCIAL1X2.5"))
    )
    (comp (ref "FID3")
      (value "FIDUCIAL1X2.5")
      (footprint "eagle-import:FIDUCIAL-1X2.5")
      (libsource (lib "eagle-import") (part "FIDUCIAL1X2.5"))
    )
    (comp (ref "FID4")
      (value "FIDUCIAL1X2.5")
      (footprint "eagle-import:FIDUCIAL-1X2.5")
      (libsource (lib "eagle-import") (part "FIDUCIAL1X2.5"))
    )
    (comp (ref "U$1")
      (value "MOUNTINGHOLE2.75")
      (footprint "eagle-import:MOUNTINGHOLE_2.75_PLATED")
      (libsource (lib "eagle-import") (part "MOUNTINGHOLE2.75"))
    )
    (comp (ref "U$2")
      (value "MOUNTINGHOLE2.75")
      (footprint "eagle-import:MOUNTINGHOLE_2.75_PLATED")
      (libsource (lib "eagle-import") (part "MOUNTINGHOLE2.75"))
    )
    (comp (ref "U$3")
      (value "MOUNTINGHOLE2.75")
      (footprint "eagle-import:MOUNTINGHOLE_2.75_PLATED")
      (libsource (lib "eagle-import") (part "MOUNTINGHOLE2.75"))
    )
    (comp (ref "U$4")
      (value "MOUNTINGHOLE2.75")
      (footprint "eagle-import:MOUNTINGHOLE_2.75_PLATED")
      (libsource (lib "eagle-import") (part "MOUNTINGHOLE2.75"))
    )
    (comp (ref "PAD1")
      (value "SMD2")
      (footprint "eagle-import:SMD1,27-2,54")
      (libsource (lib "eagle-import") (part "SMD2"))
    )
    (comp (ref "PAD2")
      (value "SMD2")
      (footprint "eagle-import:SMD1,27-2,54")
      (libsource (lib "eagle-import") (part "SMD2"))
    )
    (comp (ref "PAD3")
      (value "SMD2")
      (footprint "eagle-import:SMD1,27-2,54")
      (libsource (lib "eagle-import") (part "SMD2"))
    )
    (comp (ref "PAD4")
      (value "SMD2")
      (footprint "eagle-import:SMD1,27-2,54")
      (libsource (lib "eagle-import") (part "SMD2"))
    )
    (comp (ref "PAD5")
      (value "SMD2")
      (footprint "eagle-import:SMD1,27-2,54")
      (libsource (lib "eagle-import") (part "SMD2"))
    )
    (comp (ref "PAD6")
      (value "SMD2")
      (footprint "eagle-import:SMD1,27-2,54")
      (libsource (lib "eagle-import") (part "SMD2"))
    )
    (comp (ref "SJ1")
      (value "SOLDERJUMPERTRACE")
      (footprint "eagle-import:SJ_2S-TRACE")
      (libsource (lib "eagle-import") (part "SOLDERJUMPERTRACE"))
    )
    (comp (ref "SJ2")
      (value "SOLDERJUMPERTRACE")
      (footprint "eagle-import:SJ_2S-TRACE")
      (libsource (lib "eagle-import") (part "SOLDERJUMPERTRACE"))
    )
    (comp (ref "SJ3")
      (value "SOLDERJUMPERNO")
      (footprint "eagle-import:SJ_2S-NO")
      (libsource (lib "eagle-import") (part "SOLDERJUMPERNO"))
    )
    (comp (ref "SJ8")
      (value "SOLDERJUMPERTRACE")
      (footprint "eagle-import:SJ_2S-TRACE")
      (libsource (lib "eagle-import") (part "SOLDERJUMPERTRACE"))
    )
    (comp (ref "SJ9")
      (value "SOLDERJUMPERTRACE")
      (footprint "eagle-import:SJ_2S-TRACE")
      (libsource (lib "eagle-import") (part "SOLDERJUMPERTRACE"))
    )
    (comp (ref "SJ10")
      (value "SOLDERJUMPERTRACE")
      (footprint "eagle-import:SJ_2S-TRACE")
      (libsource (lib "eagle-import") (part "SOLDERJUMPERTRACE"))
    )
    (comp (ref "SJ11")
      (value "SOLDERJUMPERTRACE")
      (footprint "eagle-import:SJ_2S-TRACE")
      (libsource (lib "eagle-import") (part "SOLDERJUMPERTRACE"))
    )
    (comp (ref "SJ12")
      (value "SOLDERJUMPERTRACE")
      (footprint "eagle-import:SJ_2S-TRACE")
      (libsource (lib "eagle-import") (part "SOLDERJUMPERTRACE"))
    )
    (comp (ref "TP10")
      (value "PTR1B1,27")
      (footprint "eagle-import:B1,27")
      (libsource (lib "eagle-import") (part "PTR1B1,27"))
    )
    (comp (ref "TP12")
      (value "PTR1B1,27")
      (footprint "eagle-import:B1,27")
      (libsource (lib "eagle-import") (part "PTR1B1,27"))
    )
    (comp (ref "TP13")
      (value "PTR1B1,27")
      (footprint "eagle-import:B1,27")
      (libsource (lib "eagle-import") (part "PTR1B1,27"))
    )
    (comp (ref "TP16")
      (value "PTR1B1,27")
      (footprint "eagle-import:B1,27")
      (libsource (lib "eagle-import") (part "PTR1B1,27"))
    )
    (comp (ref "TP17")
      (value "PTR1B1,27")
      (footprint "eagle-import:B1,27")
      (libsource (lib "eagle-import") (part "PTR1B1,27"))
    )
    (comp (ref "U7")
      (value "Tiny85-20-SMT")
      (footprint "eagle-import:SO08-EIAJ_MCU")
      (libsource (lib "eagle-import") (part "ATTINY45TINY85-20-SMT"))
    )
  )
  (nets
    (net (code "1") (name "+1V8") (class "Default")
      (node (ref "C1") (pin "2") (pinfunction "P$2_2") (pintype "passive"))
      (node (ref "C12") (pin "1") (pinfunction "P$1_1") (pintype "passive"))
      (node (ref "C9") (pin "1") (pinfunction "P$1_1") (pintype "passive"))
      (node (ref "IC2") (pin "1") (pinfunction "VDD_1") (pintype "power_in"))
      (node (ref "IC2") (pin "6") (pinfunction "CS_6") (pintype "input"))
      (node (ref "R18") (pin "2") (pinfunction "2_2") (pintype "passive"))
      (node (ref "R8") (pin "2") (pinfunction "2_2") (pintype "passive"))
      (node (ref "R9") (pin "2") (pinfunction "2_2") (pintype "passive"))
      (node (ref "TP4") (pin "TP") (pinfunction "TP_TP") (pintype "input"))
      (node (ref "U2") (pin "2") (pinfunction "VREF1_2") (pintype "bidirectional"))
      (node (ref "U5") (pin "5") (pinfunction "VOUT_5") (pintype "power_in"))
    )
    (net (code "2") (name "+3V3") (class "Default")
      (node (ref "C11") (pin "1") (pinfunction "P$1_1") (pintype "passive"))
      (node (ref "C15") (pin "1") (pinfunction "P$1_1") (pintype "passive"))
      (node (ref "C18") (pin "1") (pinfunction "P$1_1") (pintype "passive"))
      (node (ref "C20") (pin "1") (pinfunction "P$1_1") (pintype "passive"))
      (node (ref "C4") (pin "1") (pinfunction "P$1_1") (pintype "passive"))
      (node (ref "IC3") (pin "5") (pinfunction "VOUT_5") (pintype "bidirectional"))
      (node (ref "PAD2") (pin "1") (pinfunction "P_1") (pintype "passive"))
      (node (ref "Q2") (pin "1") (pinfunction "G_1") (pintype "bidirectional"))
      (node (ref "Q3") (pin "1") (pinfunction "G_1") (pintype "bidirectional"))
      (node (ref "R11") (pin "1") (pinfunction "1_1") (pintype "passive"))
      (node (ref "R12") (pin "1") (pinfunction "1_1") (pintype "passive"))
      (node (ref "R13") (pin "1") (pinfunction "1_1") (pintype "passive"))
      (node (ref "R2") (pin "2") (pinfunction "2_2") (pintype "passive"))
      (node (ref "R3") (pin "2") (pinfunction "2_2") (pintype "passive"))
      (node (ref "R4") (pin "2") (pinfunction "2_2") (pintype "passive"))
      (node (ref "R5") (pin "2") (pinfunction "2_2") (pintype "passive"))
      (node (ref "R7") (pin "2") (pinfunction "2_2") (pintype "passive"))
      (node (ref "TP5") (pin "TP") (pinfunction "TP_TP") (pintype "input"))
      (node (ref "U1") (pin "8") (pinfunction "VCC_8") (pintype "power_in"))
      (node (ref "U5") (pin "1") (pinfunction "VIN_1") (pintype "power_in"))
      (node (ref "U5") (pin "3") (pinfunction "CE_3") (pintype "input"))
      (node (ref "U6") (pin "12") (pinfunction "FORCEON_12") (pintype "bidirectional"))
      (node (ref "U6") (pin "15") (pinfunction "VCC_15") (pintype "bidirectional"))
      (node (ref "U6") (pin "16") (pinfunction "\\~{FORCEOFF}_16") (pintype "bidirectional"))
      (node (ref "U7") (pin "8") (pinfunction "VCC_8") (pintype "bidirectional"))
    )
    (net (code "3") (name "+5V0") (class "Default")
      (node (ref "C19") (pin "1") (pinfunction "P$1_1") (pintype "passive"))
      (node (ref "C6") (pin "1") (pinfunction "P$1_1") (pintype "passive"))
      (node (ref "C7") (pin "1") (pinfunction "P$1_1") (pintype "passive"))
      (node (ref "D2") (pin "A") (pinfunction "A_A") (pintype "passive"))
      (node (ref "L1") (pin "2") (pinfunction "2_2") (pintype "passive"))
      (node (ref "R10") (pin "2") (pinfunction "2_2") (pintype "passive"))
      (node (ref "R15") (pin "2") (pinfunction "2_2") (pintype "passive"))
      (node (ref "R16") (pin "2") (pinfunction "2_2") (pintype "passive"))
      (node (ref "TP8") (pin "TP") (pinfunction "TP_TP") (pintype "input"))
      (node (ref "U3") (pin "12") (pinfunction "IO-VDD_12") (pintype "power_in"))
      (node (ref "U3") (pin "3") (pinfunction "V-REF-H_3") (pintype "input"))
      (node (ref "U3") (pin "4") (pinfunction "VDD_4") (pintype "power_in"))
    )
    (net (code "4") (name "485EN") (class "Default")
      (node (ref "R4") (pin "1") (pinfunction "1_1") (pintype "passive"))
      (node (ref "R5") (pin "1") (pinfunction "1_1") (pintype "passive"))
      (node (ref "SJ2") (pin "2") (pinfunction "2_2") (pintype "passive"))
      (node (ref "TP18") (pin "TP") (pinfunction "TP_TP") (pintype "input"))
      (node (ref "U1") (pin "2") (pinfunction "~{RE}_2") (pintype "input"))
      (node (ref "U1") (pin "3") (pinfunction "DE_3") (pintype "input"))
    )
    (net (code "5") (name "A") (class "Default")
      (node (ref "JP1") (pin "3") (pinfunction "3_3") (pintype "passive"))
      (node (ref "R1") (pin "2") (pinfunction "2_2") (pintype "passive"))
      (node (ref "R3") (pin "1") (pinfunction "1_1") (pintype "passive"))
      (node (ref "TP6") (pin "TP") (pinfunction "TP_TP") (pintype "input"))
      (node (ref "U1") (pin "6") (pinfunction "A_6") (pintype "input"))
    )
    (net (code "6") (name "A-OUT-1") (class "Default")
      (node (ref "JP2") (pin "2") (pinfunction "2_2") (pintype "passive"))
      (node (ref "X2") (pin "3") (pinfunction "K_3") (pintype "passive"))
    )
    (net (code "7") (name "A-OUT-2") (class "Default")
      (node (ref "JP3") (pin "2") (pinfunction "2_2") (pintype "passive"))
      (node (ref "X2") (pin "4") (pinfunction "K_4") (pintype "passive"))
    )
    (net (code "8") (name "B") (class "Default")
      (node (ref "R1") (pin "1") (pinfunction "1_1") (pintype "passive"))
      (node (ref "R6") (pin "1") (pinfunction "1_1") (pintype "passive"))
      (node (ref "SJ6") (pin "2") (pinfunction "2_2") (pintype "passive"))
      (node (ref "TP11") (pin "TP") (pinfunction "TP_TP") (pintype "input"))
      (node (ref "U1") (pin "7") (pinfunction "B_7") (pintype "input"))
    )
    (net (code "9") (name "B0") (class "Default")
      (node (ref "SJ3") (pin "1") (pinfunction "1_1") (pintype "passive"))
      (node (ref "SJ8") (pin "1") (pinfunction "1_1") (pintype "passive"))
      (node (ref "TP12") (pin "TP") (pinfunction "TP_TP") (pintype "input"))
      (node (ref "U7") (pin "5") (pinfunction "PB0(MOSI)_5") (pintype "bidirectional"))
    )
    (net (code "10") (name "B1") (class "Default")
      (node (ref "SJ11") (pin "1") (pinfunction "1_1") (pintype "passive"))
      (node (ref "SJ2") (pin "1") (pinfunction "1_1") (pintype "passive"))
      (node (ref "TP13") (pin "TP") (pinfunction "TP_TP") (pintype "input"))
      (node (ref "U7") (pin "6") (pinfunction "PB1(MISO)_6") (pintype "bidirectional"))
    )
    (net (code "11") (name "B2") (class "Default")
      (node (ref "SJ10") (pin "1") (pinfunction "1_1") (pintype "passive"))
      (node (ref "SJ9") (pin "1") (pinfunction "1_1") (pintype "passive"))
      (node (ref "TP10") (pin "TP") (pinfunction "TP_TP") (pintype "input"))
      (node (ref "U7") (pin "7") (pinfunction "PB2(SCK/ADC1)_7") (pintype "bidirectional"))
    )
    (net (code "12") (name "B3") (class "Default")
      (node (ref "SJ12") (pin "1") (pinfunction "1_1") (pintype "passive"))
      (node (ref "TP17") (pin "TP") (pinfunction "TP_TP") (pintype "input"))
      (node (ref "U7") (pin "2") (pinfunction "PB3(ADC3)_2") (pintype "bidirectional"))
    )
    (net (code "13") (name "B4") (class "Default")
      (node (ref "SJ1") (pin "1") (pinfunction "1_1") (pintype "passive"))
      (node (ref "TP16") (pin "TP") (pinfunction "TP_TP") (pintype "input"))
      (node (ref "U7") (pin "3") (pinfunction "PB4(ADC2)_3") (pintype "bidirectional"))
    )
    (net (code "14") (name "BASE") (class "Default")
      (node (ref "Q1") (pin "1") (pinfunction "B_1") (pintype "passive"))
      (node (ref "U4") (pin "6") (pinfunction "BASE_6") (pintype "output"))
    )
    (net (code "15") (name "C1+") (class "Default")
      (node (ref "C16") (pin "1") (pinfunction "P$1_1") (pintype "passive"))
      (node (ref "U6") (pin "2") (pinfunction "C1+_2") (pintype "bidirectional"))
    )
    (net (code "16") (name "C1-") (class "Default")
      (node (ref "C16") (pin "2") (pinfunction "P$2_2") (pintype "passive"))
      (node (ref "U6") (pin "4") (pinfunction "C1-_4") (pintype "bidirectional"))
    )
    (net (code "17") (name "C2+") (class "Default")
      (node (ref "C14") (pin "1") (pinfunction "P$1_1") (pintype "passive"))
      (node (ref "U6") (pin "5") (pinfunction "C2+_5") (pintype "bidirectional"))
    )
    (net (code "18") (name "C2-") (class "Default")
      (node (ref "C14") (pin "2") (pinfunction "P$2_2") (pintype "passive"))
      (node (ref "U6") (pin "6") (pinfunction "C2-_6") (pintype "bidirectional"))
    )
    (net (code "19") (name "COLLECTOR") (class "Default")
      (node (ref "JP3") (pin "3") (pinfunction "3_3") (pintype "passive"))
      (node (ref "Q1") (pin "3") (pinfunction "C_3") (pintype "passive"))
      (node (ref "U4") (pin "7") (pinfunction "V+_7") (pintype "input"))
    )
    (net (code "20") (name "D-OUT-1") (class "Default")
      (node (ref "SJ6") (pin "1") (pinfunction "1_1") (pintype "passive"))
      (node (ref "SJ7") (pin "1") (pinfunction "1_1") (pintype "passive"))
      (node (ref "X2") (pin "2") (pinfunction "K_2") (pintype "passive"))
    )
    (net (code "21") (name "D-OUT-2") (class "Default")
      (node (ref "JP1") (pin "2") (pinfunction "2_2") (pintype "passive"))
      (node (ref "X2") (pin "1") (pinfunction "K_1") (pintype "passive"))
    )
    (net (code "22") (name "DIN") (class "Default")
      (node (ref "R7") (pin "1") (pinfunction "1_1") (pintype "passive"))
      (node (ref "SJ1") (pin "2") (pinfunction "2_2") (pintype "passive"))
      (node (ref "U1") (pin "4") (pinfunction "DI_4") (pintype "input"))
      (node (ref "U6") (pin "11") (pinfunction "DIN_11") (pintype "bidirectional"))
    )
    (net (code "23") (name "DOUT") (class "Default")
      (node (ref "JP1") (pin "1") (pinfunction "1_1") (pintype "passive"))
      (node (ref "TP14") (pin "TP") (pinfunction "TP_TP") (pintype "input"))
      (node (ref "U6") (pin "13") (pinfunction "DOUT_13") (pintype "bidirectional"))
    )
    (net (code "24") (name "EMITTER") (class "Default")
      (node (ref "Q1") (pin "2") (pinfunction "E_2") (pintype "passive"))
      (node (ref "U4") (pin "5") (pinfunction "EMITTER_5") (pintype "input"))
    )
    (net (code "25") (name "GND") (class "Default")
      (node (ref "C1") (pin "1") (pinfunction "P$1_1") (pintype "passive"))
      (node (ref "C10") (pin "2") (pinfunction "P$2_2") (pintype "passive"))
      (node (ref "C11") (pin "2") (pinfunction "P$2_2") (pintype "passive"))
      (node (ref "C12") (pin "2") (pinfunction "P$2_2") (pintype "passive"))
      (node (ref "C13") (pin "2") (pinfunction "P$2_2") (pintype "passive"))
      (node (ref "C15") (pin "2") (pinfunction "P$2_2") (pintype "passive"))
      (node (ref "C17") (pin "2") (pinfunction "P$2_2") (pintype "passive"))
      (node (ref "C18") (pin "2") (pinfunction "P$2_2") (pintype "passive"))
      (node (ref "C19") (pin "2") (pinfunction "P$2_2") (pintype "passive"))
      (node (ref "C20") (pin "2") (pinfunction "P$2_2") (pintype "passive"))
      (node (ref "C3") (pin "1") (pinfunction "P$1_1") (pintype "passive"))
      (node (ref "C4") (pin "2") (pinfunction "P$2_2") (pintype "passive"))
      (node (ref "C5") (pin "2") (pinfunction "P$2_2") (pintype "passive"))
      (node (ref "C6") (pin "2") (pinfunction "P$2_2") (pintype "passive"))
      (node (ref "C7") (pin "2") (pinfunction "P$2_2") (pintype "passive"))
      (node (ref "C8") (pin "2") (pinfunction "P$2_2") (pintype "passive"))
      (node (ref "C9") (pin "2") (pinfunction "P$2_2") (pintype "passive"))
      (node (ref "D1") (pin "A") (pinfunction "A_A") (pintype "passive"))
      (node (ref "IC1") (pin "6") (pinfunction "GND_6") (pintype "power_in"))
      (node (ref "IC2") (pin "7") (pinfunction "GND_7") (pintype "power_in"))
      (node (ref "IC3") (pin "2") (pinfunction "GND_2") (pintype "bidirectional"))
      (node (ref "JP3") (pin "1") (pinfunction "1_1") (pintype "passive"))
      (node (ref "PAD6") (pin "1") (pinfunction "P_1") (pintype "passive"))
      (node (ref "R14") (pin "1") (pinfunction "1_1") (pintype "passive"))
      (node (ref "R18") (pin "1") (pinfunction "1_1") (pintype "passive"))
      (node (ref "R19") (pin "2") (pinfunction "2_2") (pintype "passive"))
      (node (ref "R6") (pin "2") (pinfunction "2_2") (pintype "passive"))
      (node (ref "TP9") (pin "TP") (pinfunction "TP_TP") (pintype "input"))
      (node (ref "U1") (pin "5") (pinfunction "GND_5") (pintype "passive"))
      (node (ref "U2") (pin "1") (pinfunction "GND_1") (pintype "bidirectional"))
      (node (ref "U3") (pin "13") (pinfunction "A0_13") (pintype "input"))
      (node (ref "U3") (pin "14") (pinfunction "A1_14") (pintype "input"))
      (node (ref "U3") (pin "15") (pinfunction "A2_15") (pintype "input"))
      (node (ref "U3") (pin "16") (pinfunction "A3_16") (pintype "input"))
      (node (ref "U3") (pin "5") (pinfunction "V-REF-L_5") (pintype "input"))
      (node (ref "U3") (pin "6") (pinfunction "GND_6") (pintype "power_in"))
      (node (ref "U3") (pin "9") (pinfunction "LDAC_9") (pintype "input"))
      (node (ref "U4") (pin "3") (pinfunction "I-RETURN_3") (pintype "input"))
      (node (ref "U5") (pin "2") (pinfunction "VSS_2") (pintype "power_in"))
      (node (ref "U6") (pin "1") (pinfunction "\\~{EN}_1") (pintype "bidirectional"))
      (node (ref "U6") (pin "14") (pinfunction "GND_14") (pintype "bidirectional"))
      (node (ref "U7") (pin "4") (pinfunction "GND_4") (pintype "bidirectional"))
      (node (ref "X1") (pin "2") (pinfunction "K_2") (pintype "passive"))
    )
    (net (code "26") (name "I-IN") (class "Default")
      (node (ref "R20") (pin "1") (pinfunction "1_1") (pintype "passive"))
      (node (ref "U4") (pin "2") (pinfunction "I-IN_2") (pintype "input"))
    )
    (net (code "27") (name "I-OUT") (class "Default")
      (node (ref "JP2") (pin "3") (pinfunction "3_3") (pintype "passive"))
      (node (ref "TP1") (pin "TP") (pinfunction "TP_TP") (pintype "input"))
      (node (ref "U4") (pin "4") (pinfunction "I-OUT_4") (pintype "output"))
    )
    (net (code "28") (name "MISO") (class "Default")
      (node (ref "PAD1") (pin "1") (pinfunction "P_1") (pintype "passive"))
      (node (ref "SJ11") (pin "2") (pinfunction "2_2") (pintype "passive"))
    )
    (net (code "29") (name "MOSI") (class "Default")
      (node (ref "PAD4") (pin "1") (pinfunction "P_1") (pintype "passive"))
      (node (ref "SJ8") (pin "2") (pinfunction "2_2") (pintype "passive"))
    )
    (net (code "30") (name "Net-(C2-P$2)") (class "Default")
      (node (ref "C2") (pin "2") (pinfunction "P$2_2") (pintype "passive"))
      (node (ref "IC1") (pin "1") (pinfunction "BOOT_1") (pintype "output"))
    )
    (net (code "31") (name "Net-(C3-P$2)") (class "Default")
      (node (ref "C3") (pin "2") (pinfunction "P$2_2") (pintype "passive"))
      (node (ref "R12") (pin "2") (pinfunction "2_2") (pintype "passive"))
      (node (ref "U2") (pin "7") (pinfunction "VREF2_7") (pintype "bidirectional"))
      (node (ref "U2") (pin "8") (pinfunction "EN_8") (pintype "bidirectional"))
    )
    (net (code "32") (name "Net-(C8-P$1)") (class "Default")
      (node (ref "C8") (pin "1") (pinfunction "P$1_1") (pintype "passive"))
      (node (ref "IC2") (pin "8") (pinfunction "VREF_8") (pintype "power_in"))
    )
    (net (code "33") (name "Net-(R14-Pad2)") (class "Default")
      (node (ref "R14") (pin "2") (pinfunction "2_2") (pintype "passive"))
      (node (ref "R21") (pin "1") (pinfunction "1_1") (pintype "passive"))
    )
    (net (code "34") (name "Net-(R17-Pad1)") (class "Default")
      (node (ref "R17") (pin "1") (pinfunction "1_1") (pintype "passive"))
      (node (ref "R20") (pin "2") (pinfunction "2_2") (pintype "passive"))
    )
    (net (code "35") (name "PH") (class "Default")
      (node (ref "C2") (pin "1") (pinfunction "P$1_1") (pintype "passive"))
      (node (ref "D1") (pin "C") (pinfunction "C_C") (pintype "passive"))
      (node (ref "IC1") (pin "8") (pinfunction "PH_8") (pintype "output"))
      (node (ref "L1") (pin "1") (pinfunction "1_1") (pintype "passive"))
    )
    (net (code "36") (name "RESET") (class "Default")
      (node (ref "PAD5") (pin "1") (pinfunction "P_1") (pintype "passive"))
      (node (ref "U7") (pin "1") (pinfunction "PB5(NRES)_1") (pintype "bidirectional"))
    )
    (net (code "37") (name "RIN") (class "Default")
      (node (ref "SJ7") (pin "2") (pinfunction "2_2") (pintype "passive"))
      (node (ref "TP15") (pin "TP") (pinfunction "TP_TP") (pintype "input"))
      (node (ref "U6") (pin "8") (pinfunction "RIN_8") (pintype "bidirectional"))
    )
    (net (code "38") (name "ROUT") (class "Default")
      (node (ref "R2") (pin "1") (pinfunction "1_1") (pintype "passive"))
      (node (ref "SJ12") (pin "2") (pinfunction "2_2") (pintype "passive"))
      (node (ref "U1") (pin "1") (pinfunction "RO_1") (pintype "output"))
      (node (ref "U6") (pin "9") (pinfunction "ROUT_9") (pintype "bidirectional"))
    )
    (net (code "39") (name "SA0") (class "Default")
      (node (ref "IC2") (pin "3") (pinfunction "SA0_3") (pintype "input"))
      (node (ref "R19") (pin "1") (pinfunction "1_1") (pintype "passive"))
    )
    (net (code "40") (name "SCK") (class "Default")
      (node (ref "PAD3") (pin "1") (pinfunction "P_1") (pintype "passive"))
      (node (ref "SJ10") (pin "2") (pinfunction "2_2") (pintype "passive"))
    )
    (net (code "41") (name "SCL_1V8") (class "Default")
      (node (ref "IC2") (pin "4") (pinfunction "SCK_4") (pintype "bidirectional"))
      (node (ref "R8") (pin "1") (pinfunction "1_1") (pintype "passive"))
      (node (ref "U2") (pin "3") (pinfunction "SCL1_3") (pintype "bidirectional"))
    )
    (net (code "42") (name "SCL_3V3") (class "Default")
      (node (ref "Q3") (pin "2") (pinfunction "S_2") (pintype "bidirectional"))
      (node (ref "R13") (pin "2") (pinfunction "2_2") (pintype "passive"))
      (node (ref "SJ9") (pin "2") (pinfunction "2_2") (pintype "passive"))
      (node (ref "U2") (pin "6") (pinfunction "SCL2_6") (pintype "bidirectional"))
    )
    (net (code "43") (name "SCL_5V0") (class "Default")
      (node (ref "Q3") (pin "3") (pinfunction "D_3") (pintype "bidirectional"))
      (node (ref "R15") (pin "1") (pinfunction "1_1") (pintype "passive"))
      (node (ref "U3") (pin "10") (pinfunction "SCK_10") (pintype "bidirectional"))
    )
    (net (code "44") (name "SDA_1V8") (class "Default")
      (node (ref "IC2") (pin "5") (pinfunction "SDA_5") (pintype "bidirectional"))
      (node (ref "R9") (pin "1") (pinfunction "1_1") (pintype "passive"))
      (node (ref "U2") (pin "4") (pinfunction "SDA1_4") (pintype "bidirectional"))
    )
    (net (code "45") (name "SDA_3V3") (class "Default")
      (node (ref "Q2") (pin "2") (pinfunction "S_2") (pintype "bidirectional"))
      (node (ref "R11") (pin "2") (pinfunction "2_2") (pintype "passive"))
      (node (ref "SJ3") (pin "2") (pinfunction "2_2") (pintype "passive"))
      (node (ref "U2") (pin "5") (pinfunction "SDA2_5") (pintype "bidirectional"))
    )
    (net (code "46") (name "SDA_5V0") (class "Default")
      (node (ref "Q2") (pin "3") (pinfunction "D_3") (pintype "bidirectional"))
      (node (ref "R16") (pin "1") (pinfunction "1_1") (pintype "passive"))
      (node (ref "U3") (pin "11") (pinfunction "SDA_11") (pintype "bidirectional"))
    )
    (net (code "47") (name "V+") (class "Default")
      (node (ref "C17") (pin "1") (pinfunction "P$1_1") (pintype "passive"))
      (node (ref "U6") (pin "3") (pinfunction "V+_3") (pintype "bidirectional"))
    )
    (net (code "48") (name "V-") (class "Default")
      (node (ref "C13") (pin "1") (pinfunction "P$1_1") (pintype "passive"))
      (node (ref "U6") (pin "7") (pinfunction "V-_7") (pintype "bidirectional"))
    )
    (net (code "49") (name "V-OUT-1") (class "Default")
      (node (ref "JP2") (pin "1") (pinfunction "1_1") (pintype "passive"))
      (node (ref "TP3") (pin "TP") (pinfunction "TP_TP") (pintype "input"))
      (node (ref "U3") (pin "8") (pinfunction "V-OUT-D_8") (pintype "output"))
    )
    (net (code "50") (name "V-OUT-2") (class "Default")
      (node (ref "R17") (pin "2") (pinfunction "2_2") (pintype "passive"))
      (node (ref "TP19") (pin "TP") (pinfunction "TP_TP") (pintype "input"))
      (node (ref "U3") (pin "2") (pinfunction "V-OUT-B_2") (pintype "output"))
    )
    (net (code "51") (name "VIN") (class "Default")
      (node (ref "C5") (pin "1") (pinfunction "P$1_1") (pintype "passive"))
      (node (ref "IC1") (pin "7") (pinfunction "VIN_7") (pintype "input"))
      (node (ref "TP2") (pin "TP") (pinfunction "TP_TP") (pintype "input"))
      (node (ref "X1") (pin "1") (pinfunction "K_1") (pintype "passive"))
    )
    (net (code "52") (name "VIN_5V0") (class "Default")
      (node (ref "C10") (pin "1") (pinfunction "P$1_1") (pintype "passive"))
      (node (ref "D2") (pin "C") (pinfunction "C_C") (pintype "passive"))
      (node (ref "IC3") (pin "1") (pinfunction "VIN_1") (pintype "bidirectional"))
      (node (ref "IC3") (pin "3") (pinfunction "EN_3") (pintype "bidirectional"))
      (node (ref "TP7") (pin "TP") (pinfunction "TP_TP") (pintype "input"))
    )
    (net (code "53") (name "VSENSE") (class "Default")
      (node (ref "IC1") (pin "4") (pinfunction "VSENSE_4") (pintype "input"))
      (node (ref "R10") (pin "1") (pinfunction "1_1") (pintype "passive"))
      (node (ref "R21") (pin "2") (pinfunction "2_2") (pintype "passive"))
    )
    (net (code "54") (name "unconnected-(IC1-ENA-Pad5)") (class "Default")
      (node (ref "IC1") (pin "5") (pinfunction "ENA_5") (pintype "input"))
    )
    (net (code "55") (name "unconnected-(IC2-INT-Pad2)") (class "Default")
      (node (ref "IC2") (pin "2") (pinfunction "INT_2") (pintype "output"))
    )
    (net (code "56") (name "unconnected-(IC3-BYP-Pad4)") (class "Default")
      (node (ref "IC3") (pin "4") (pinfunction "BYP_4") (pintype "bidirectional"))
    )
    (net (code "57") (name "unconnected-(U3-V-OUT-A-Pad1)") (class "Default")
      (node (ref "U3") (pin "1") (pinfunction "V-OUT-A_1") (pintype "output"))
    )
    (net (code "58") (name "unconnected-(U3-V-OUT-C-Pad7)") (class "Default")
      (node (ref "U3") (pin "7") (pinfunction "V-OUT-C_7") (pintype "output"))
    )
    (net (code "59") (name "unconnected-(U4-+5V0-Pad8)") (class "Default")
      (node (ref "U4") (pin "8") (pinfunction "+5V0_8") (pintype "no_connect"))
    )
    (net (code "60") (name "unconnected-(U5-NC-Pad4)") (class "Default")
      (node (ref "U5") (pin "4") (pinfunction "NC_4") (pintype "no_connect"))
    )
    (net (code "61") (name "unconnected-(U6-\\~{INV}-Pad10)") (class "Default")
      (node (ref "U6") (pin "10") (pinfunction "\\~{INV}_10") (pintype "bidirectional"))
    )
  )
)
